# frontend.net
KiCad netlist of a schematic drawn in EAGLE
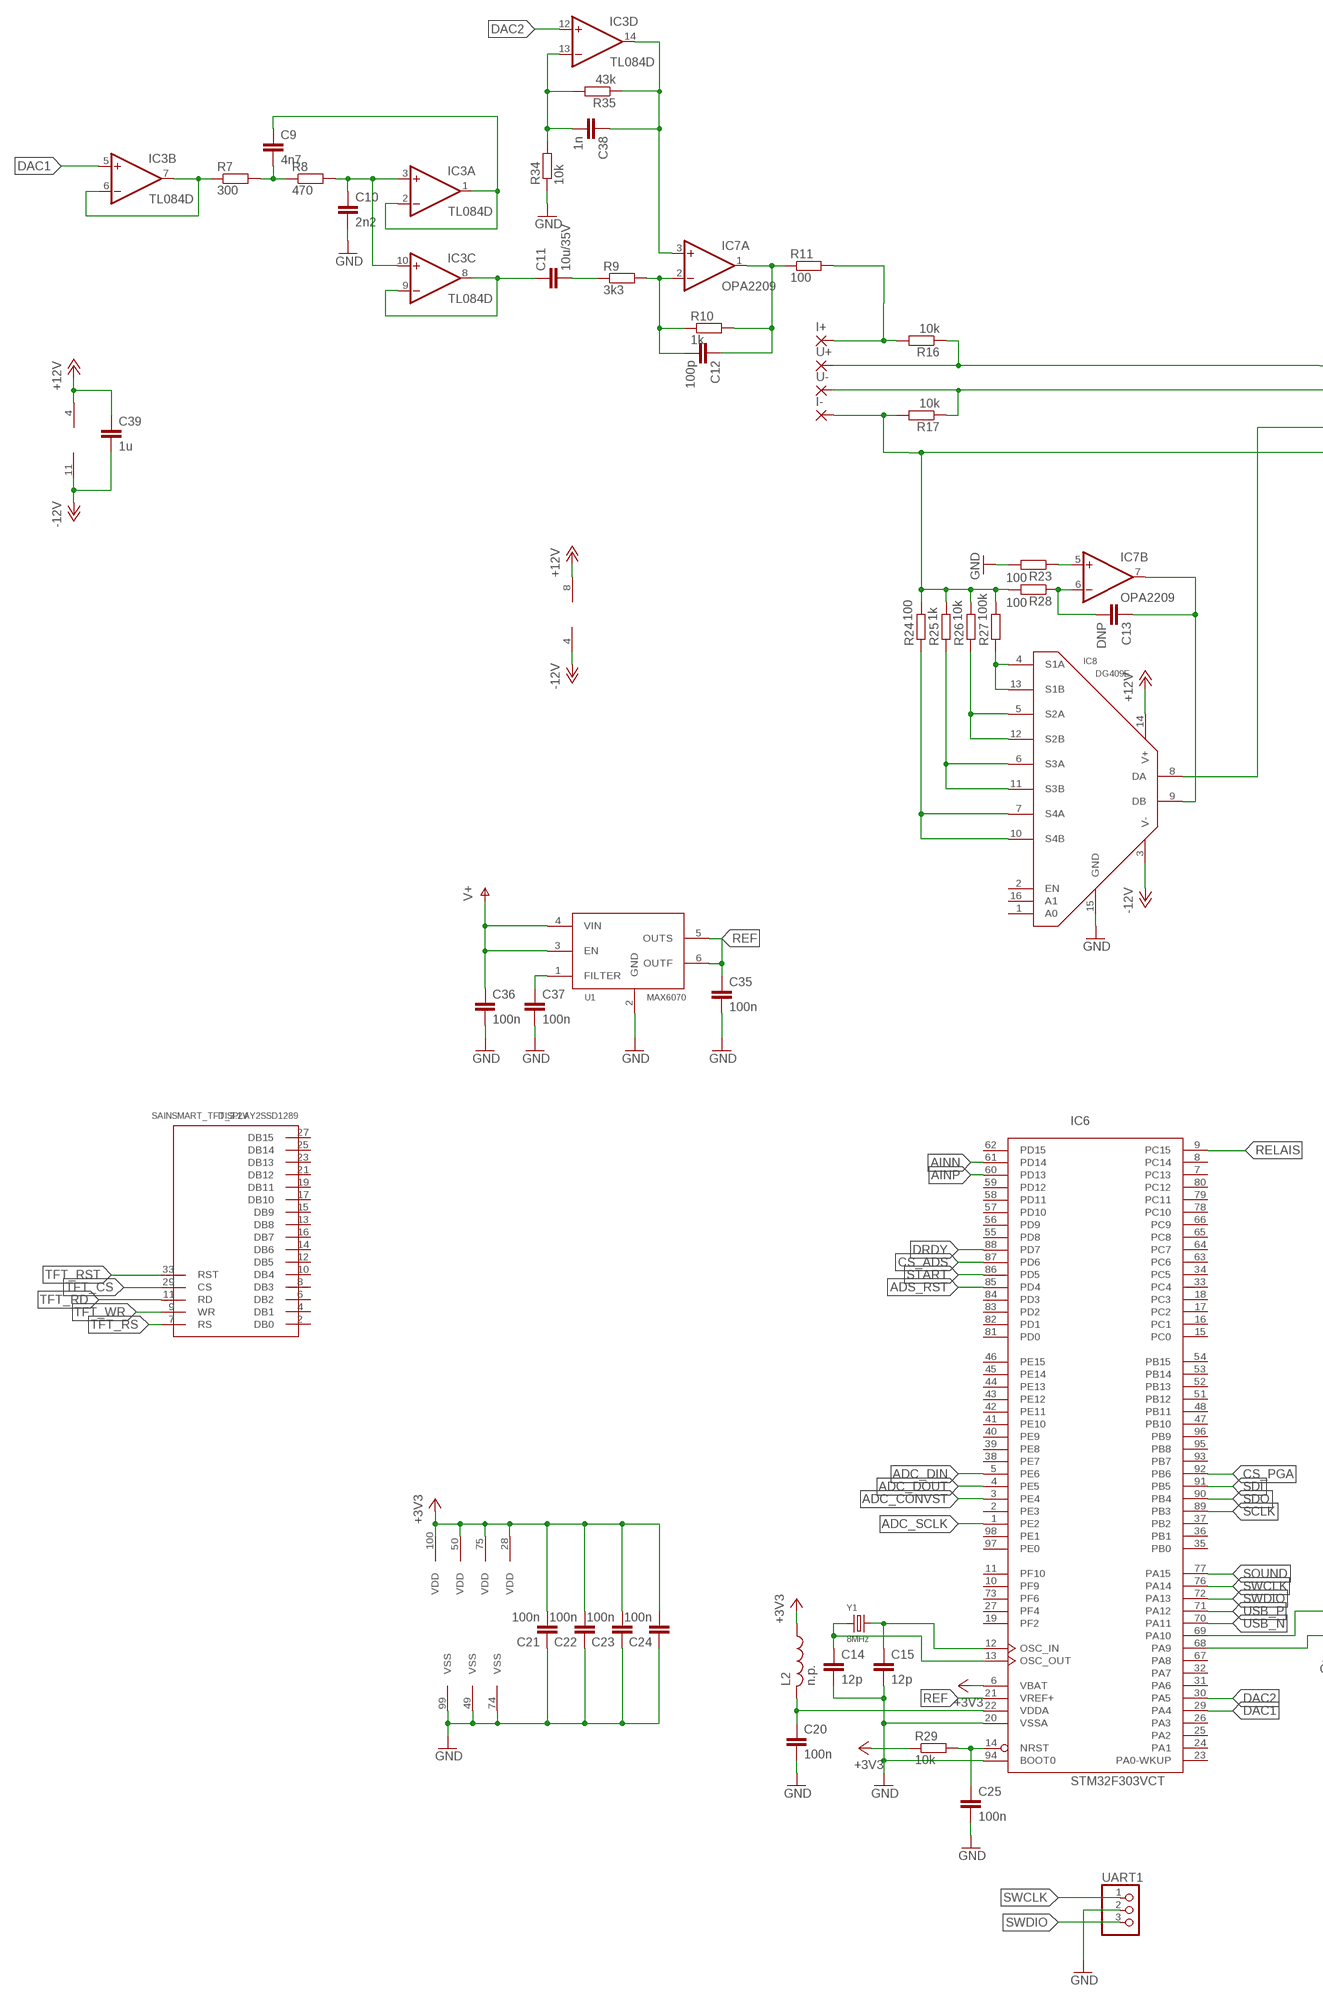
[diagram p0: schematic, sheet 1, part 1 of 2]
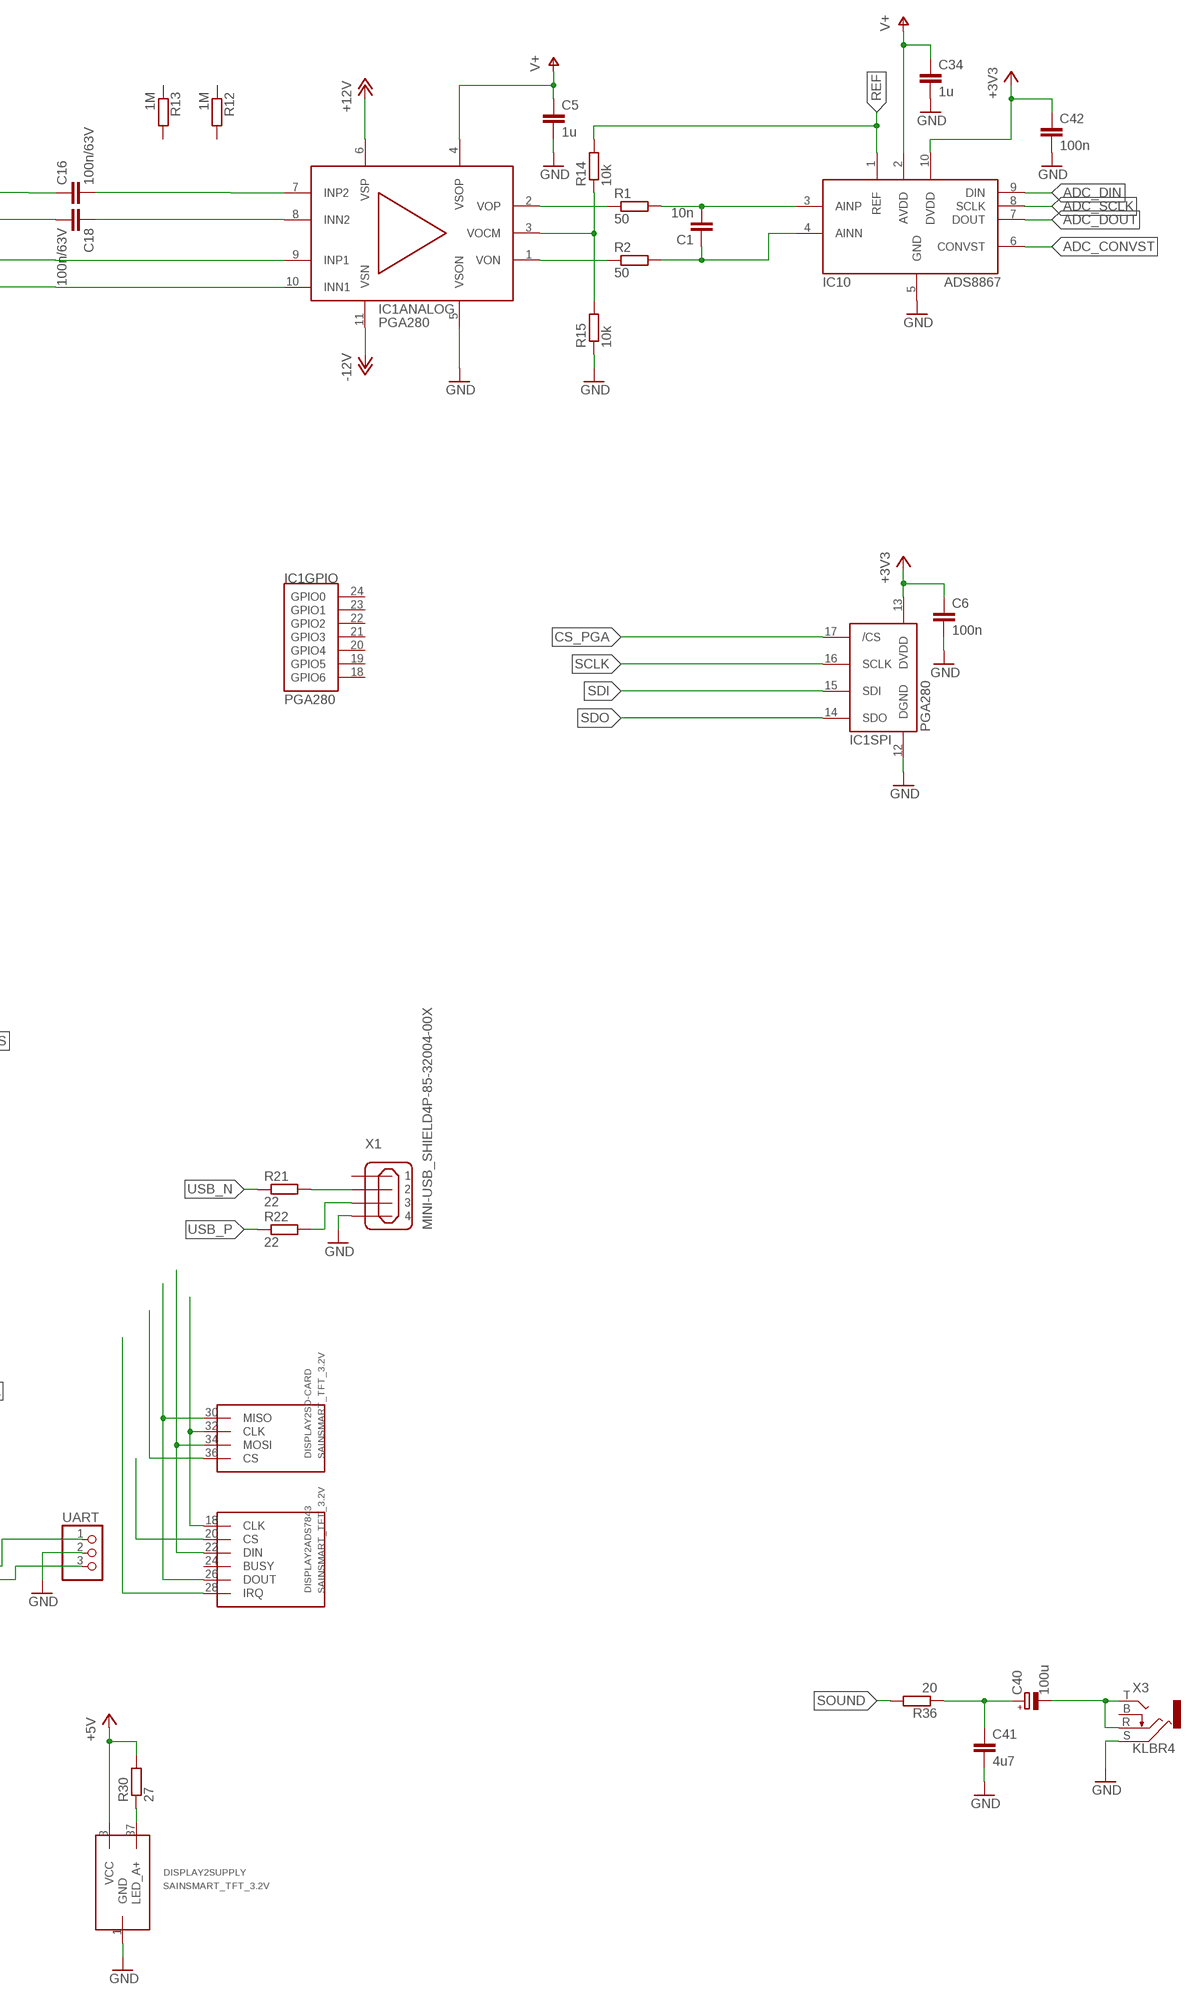
[diagram p1: schematic, sheet 1, part 2 of 2]
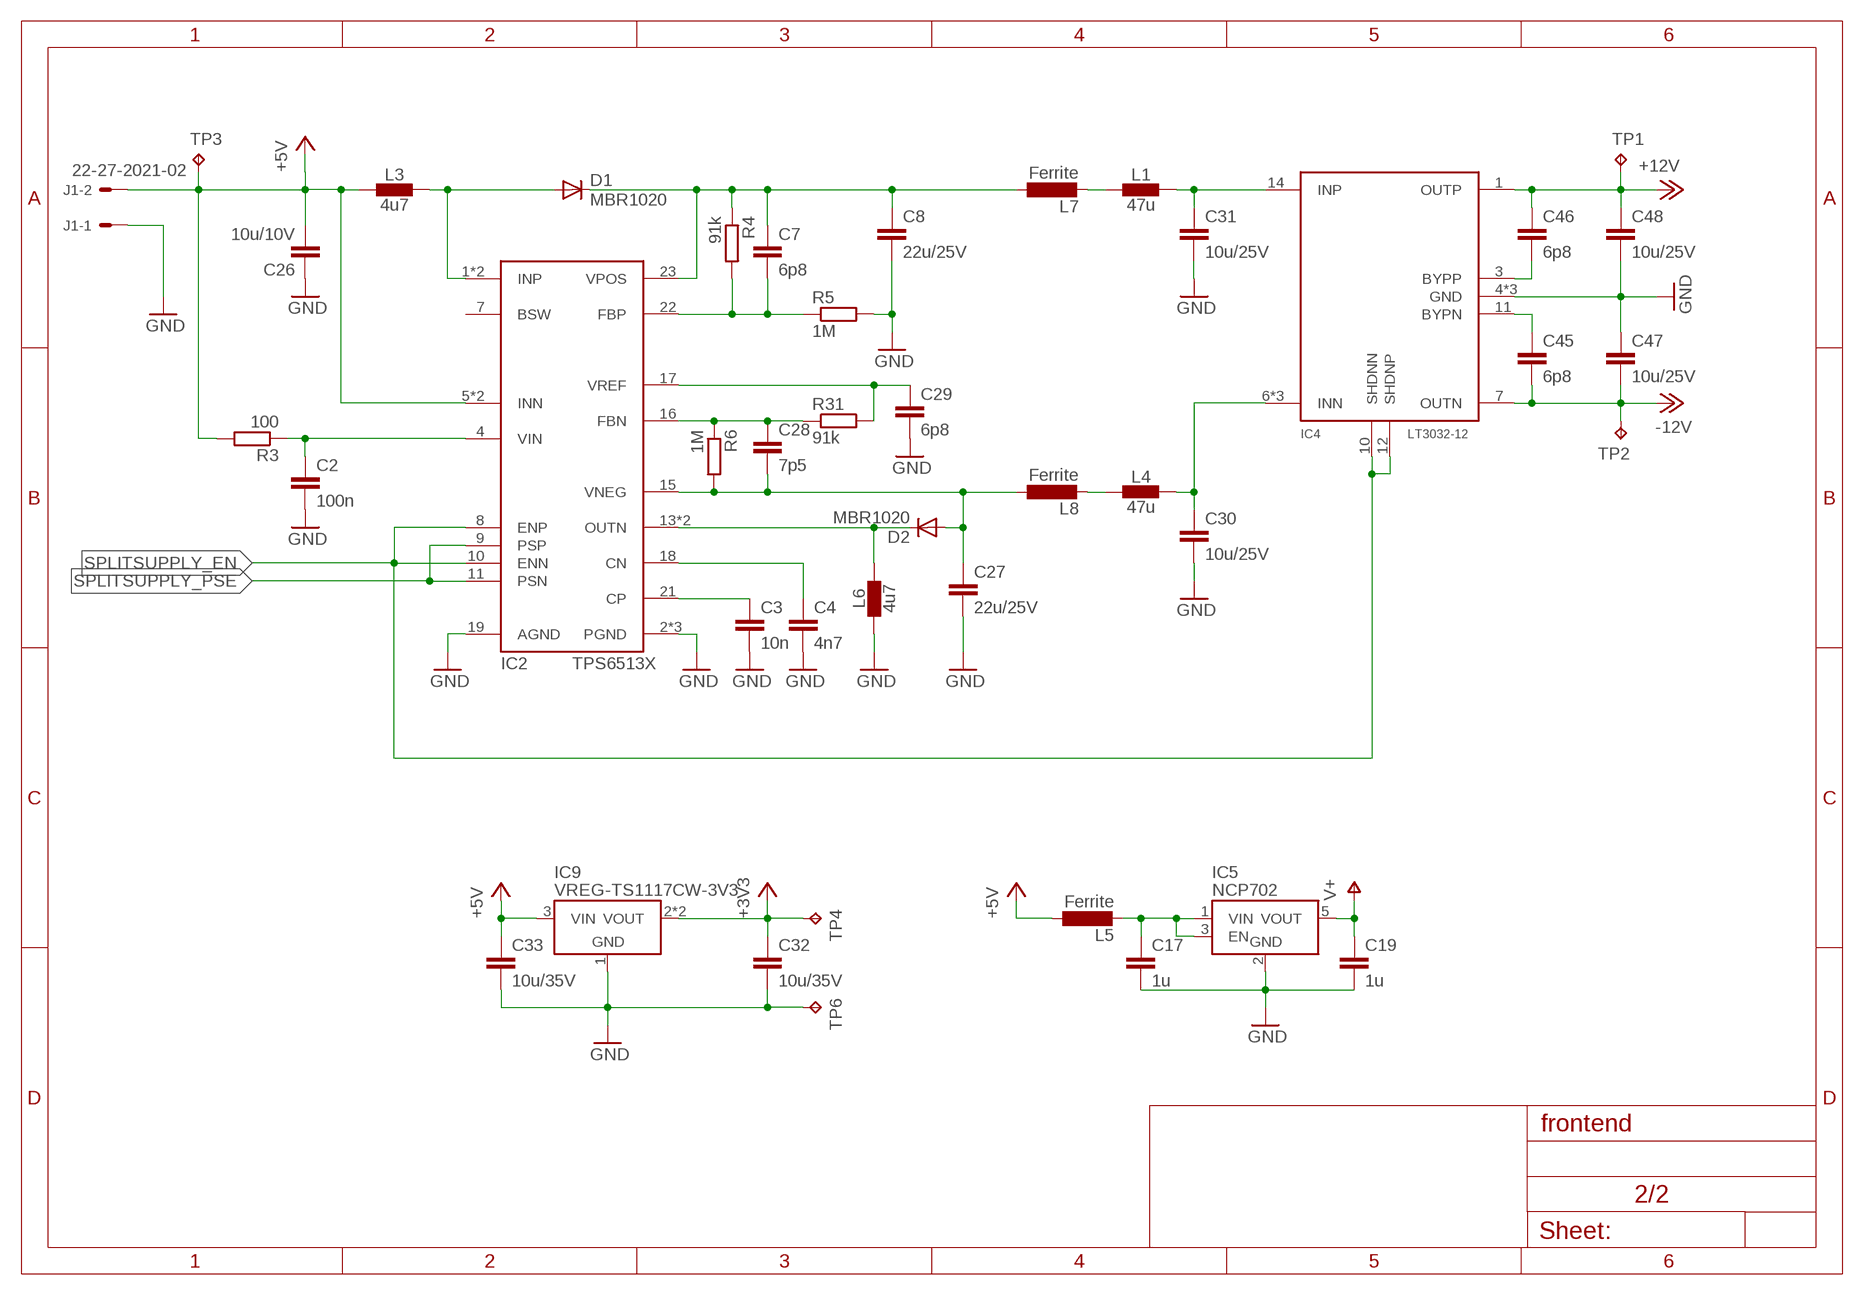
[diagram p2: schematic, sheet 2]

(export (version "E")
  (design (tool "Eeschema 10.0.6"))
  (components
    (comp (ref "C2")
      (value "100n")
      (footprint "eagle-import:C0603K")
      (libsource (lib "eagle-import") (part "C-EUC0603K"))
    )
    (comp (ref "C3")
      (value "10n")
      (footprint "eagle-import:C0603K")
      (libsource (lib "eagle-import") (part "C-EUC0603K"))
    )
    (comp (ref "C4")
      (value "4n7")
      (footprint "eagle-import:C0603K")
      (libsource (lib "eagle-import") (part "C-EUC0603K"))
    )
    (comp (ref "C7")
      (value "6p8")
      (footprint "eagle-import:C0603K")
      (libsource (lib "eagle-import") (part "C-EUC0603K"))
    )
    (comp (ref "C8")
      (value "22u/25V")
      (footprint "eagle-import:C1206K")
      (libsource (lib "eagle-import") (part "C-EUC1206K"))
    )
    (comp (ref "C17")
      (value "1u")
      (footprint "eagle-import:C0603")
      (libsource (lib "eagle-import") (part "C-EUC0603"))
    )
    (comp (ref "C19")
      (value "1u")
      (footprint "eagle-import:C0603")
      (libsource (lib "eagle-import") (part "C-EUC0603"))
    )
    (comp (ref "C26")
      (value "10u/10V")
      (footprint "eagle-import:C1206K")
      (libsource (lib "eagle-import") (part "C-EUC1206K"))
    )
    (comp (ref "C27")
      (value "22u/25V")
      (footprint "eagle-import:C1206K")
      (libsource (lib "eagle-import") (part "C-EUC1206K"))
    )
    (comp (ref "C28")
      (value "7p5")
      (footprint "eagle-import:C0603K")
      (libsource (lib "eagle-import") (part "C-EUC0603K"))
    )
    (comp (ref "C29")
      (value "6p8")
      (footprint "eagle-import:C0603K")
      (libsource (lib "eagle-import") (part "C-EUC0603K"))
    )
    (comp (ref "C30")
      (value "10u/25V")
      (footprint "eagle-import:C1206K")
      (libsource (lib "eagle-import") (part "C-EUC1206K"))
    )
    (comp (ref "C31")
      (value "10u/25V")
      (footprint "eagle-import:C1206K")
      (libsource (lib "eagle-import") (part "C-EUC1206K"))
    )
    (comp (ref "C32")
      (value "10u/35V")
      (footprint "eagle-import:C1206K")
      (libsource (lib "eagle-import") (part "C-EUC1206K"))
    )
    (comp (ref "C33")
      (value "10u/35V")
      (footprint "eagle-import:C1206K")
      (libsource (lib "eagle-import") (part "C-EUC1206K"))
    )
    (comp (ref "C45")
      (value "6p8")
      (footprint "eagle-import:C0603K")
      (libsource (lib "eagle-import") (part "C-EUC0603K"))
    )
    (comp (ref "C46")
      (value "6p8")
      (footprint "eagle-import:C0603K")
      (libsource (lib "eagle-import") (part "C-EUC0603K"))
    )
    (comp (ref "C47")
      (value "10u/25V")
      (footprint "eagle-import:C1206K")
      (libsource (lib "eagle-import") (part "C-EUC1206K"))
    )
    (comp (ref "C48")
      (value "10u/25V")
      (footprint "eagle-import:C1206K")
      (libsource (lib "eagle-import") (part "C-EUC1206K"))
    )
    (comp (ref "D1")
      (value "MBR1020")
      (footprint "eagle-import:SOD123")
      (libsource (lib "eagle-import") (part "DIODE-SOD123"))
    )
    (comp (ref "D2")
      (value "MBR1020")
      (footprint "eagle-import:SOD123")
      (libsource (lib "eagle-import") (part "DIODE-SOD123"))
    )
    (comp (ref "IC2")
      (value "TPS6513X")
      (footprint "eagle-import:QFN50P400X400X100-25T250N")
      (libsource (lib "eagle-import") (part "TPS6513X"))
    )
    (comp (ref "IC4")
      (value "LT3032-12")
      (footprint "eagle-import:SON50P300X400X80-14N")
      (libsource (lib "eagle-import") (part "LT3032"))
    )
    (comp (ref "IC5")
      (value "NCP702")
      (footprint "eagle-import:SOT95P240X110-5")
      (libsource (lib "eagle-import") (part "NCP702"))
    )
    (comp (ref "IC9")
      (value "VREG-TS1117CW-3V3")
      (footprint "eagle-import:SOT223")
      (libsource (lib "eagle-import") (part "VREG-TS1117CW-3V3"))
    )
    (comp (ref "J1")
      (value "22-27-2021-02")
      (footprint "eagle-import:6410-02")
      (libsource (lib "eagle-import") (part "22-?-0227-2021"))
    )
    (comp (ref "L1")
      (value "47u")
      (footprint "eagle-import:L_1212")
      (libsource (lib "eagle-import") (part "INDUCTOR-1212"))
    )
    (comp (ref "L3")
      (value "4u7")
      (footprint "eagle-import:L_1212")
      (libsource (lib "eagle-import") (part "INDUCTOR-1212"))
    )
    (comp (ref "L4")
      (value "47u")
      (footprint "eagle-import:L_1212")
      (libsource (lib "eagle-import") (part "INDUCTOR-1212"))
    )
    (comp (ref "L5")
      (value "Ferrite")
      (footprint "eagle-import:R0603")
      (libsource (lib "eagle-import") (part "INDUCTOR0603"))
    )
    (comp (ref "L6")
      (value "4u7")
      (footprint "eagle-import:L_1212")
      (libsource (lib "eagle-import") (part "INDUCTOR-1212"))
    )
    (comp (ref "L7")
      (value "Ferrite")
      (footprint "eagle-import:R0603")
      (libsource (lib "eagle-import") (part "INDUCTOR0603"))
    )
    (comp (ref "L8")
      (value "Ferrite")
      (footprint "eagle-import:R0603")
      (libsource (lib "eagle-import") (part "INDUCTOR0603"))
    )
    (comp (ref "R3")
      (value "100")
      (footprint "eagle-import:R0603")
      (libsource (lib "eagle-import") (part "R-EU_R0603"))
    )
    (comp (ref "R4")
      (value "91k")
      (footprint "eagle-import:R0603")
      (libsource (lib "eagle-import") (part "R-EU_R0603"))
    )
    (comp (ref "R5")
      (value "1M")
      (footprint "eagle-import:R0603")
      (libsource (lib "eagle-import") (part "R-EU_R0603"))
    )
    (comp (ref "R6")
      (value "1M")
      (footprint "eagle-import:R0603")
      (libsource (lib "eagle-import") (part "R-EU_R0603"))
    )
    (comp (ref "R31")
      (value "91k")
      (footprint "eagle-import:R0603")
      (libsource (lib "eagle-import") (part "R-EU_R0603"))
    )
    (comp (ref "TP1")
      (value "TPB2,54")
      (footprint "eagle-import:B2,54")
      (libsource (lib "eagle-import") (part "TPB2,54"))
    )
    (comp (ref "TP2")
      (value "TPB2,54")
      (footprint "eagle-import:B2,54")
      (libsource (lib "eagle-import") (part "TPB2,54"))
    )
    (comp (ref "TP3")
      (value "TPB2,54")
      (footprint "eagle-import:B2,54")
      (libsource (lib "eagle-import") (part "TPB2,54"))
    )
    (comp (ref "TP4")
      (value "TPB2,54")
      (footprint "eagle-import:B2,54")
      (libsource (lib "eagle-import") (part "TPB2,54"))
    )
    (comp (ref "TP6")
      (value "TPB2,54")
      (footprint "eagle-import:B2,54")
      (libsource (lib "eagle-import") (part "TPB2,54"))
    )
    (comp (ref "C1")
      (value "10n")
      (footprint "eagle-import:C0603K")
      (libsource (lib "eagle-import") (part "C-EUC0603K"))
    )
    (comp (ref "C5")
      (value "1u")
      (footprint "eagle-import:C0603K")
      (libsource (lib "eagle-import") (part "C-EUC0603K"))
    )
    (comp (ref "C6")
      (value "100n")
      (footprint "eagle-import:C0603K")
      (libsource (lib "eagle-import") (part "C-EUC0603K"))
    )
    (comp (ref "C9")
      (value "4n7")
      (footprint "eagle-import:C0603K")
      (libsource (lib "eagle-import") (part "C-EUC0603K"))
    )
    (comp (ref "C10")
      (value "2n2")
      (footprint "eagle-import:C0603K")
      (libsource (lib "eagle-import") (part "C-EUC0603K"))
    )
    (comp (ref "C11")
      (value "10u/35V")
      (footprint "eagle-import:C1206K")
      (libsource (lib "eagle-import") (part "C-EUC1206K"))
    )
    (comp (ref "C12")
      (value "100p")
      (footprint "eagle-import:C0603K")
      (libsource (lib "eagle-import") (part "C-EUC0603K"))
    )
    (comp (ref "C13")
      (value "DNP")
      (footprint "eagle-import:C0603K")
      (libsource (lib "eagle-import") (part "C-EUC0603K"))
    )
    (comp (ref "C14")
      (value "12p")
      (footprint "eagle-import:C0603K")
      (libsource (lib "eagle-import") (part "C-EUC0603K"))
    )
    (comp (ref "C15")
      (value "12p")
      (footprint "eagle-import:C0603K")
      (libsource (lib "eagle-import") (part "C-EUC0603K"))
    )
    (comp (ref "C16")
      (value "100n/63V")
      (footprint "eagle-import:C1206K")
      (libsource (lib "eagle-import") (part "C-EUC1206K"))
    )
    (comp (ref "C18")
      (value "100n/63V")
      (footprint "eagle-import:C1206K")
      (libsource (lib "eagle-import") (part "C-EUC1206K"))
    )
    (comp (ref "C20")
      (value "100n")
      (footprint "eagle-import:C0603K")
      (libsource (lib "eagle-import") (part "C-EUC0603K"))
    )
    (comp (ref "C21")
      (value "100n")
      (footprint "eagle-import:C0603K")
      (libsource (lib "eagle-import") (part "C-EUC0603K"))
    )
    (comp (ref "C22")
      (value "100n")
      (footprint "eagle-import:C0603K")
      (libsource (lib "eagle-import") (part "C-EUC0603K"))
    )
    (comp (ref "C23")
      (value "100n")
      (footprint "eagle-import:C0603K")
      (libsource (lib "eagle-import") (part "C-EUC0603K"))
    )
    (comp (ref "C24")
      (value "100n")
      (footprint "eagle-import:C0603K")
      (libsource (lib "eagle-import") (part "C-EUC0603K"))
    )
    (comp (ref "C25")
      (value "100n")
      (footprint "eagle-import:C0603K")
      (libsource (lib "eagle-import") (part "C-EUC0603K"))
    )
    (comp (ref "C34")
      (value "1u")
      (footprint "eagle-import:C0603K")
      (libsource (lib "eagle-import") (part "C-EUC0603K"))
    )
    (comp (ref "C35")
      (value "100n")
      (footprint "eagle-import:C0603K")
      (libsource (lib "eagle-import") (part "C-EUC0603K"))
    )
    (comp (ref "C36")
      (value "100n")
      (footprint "eagle-import:C0603K")
      (libsource (lib "eagle-import") (part "C-EUC0603K"))
    )
    (comp (ref "C37")
      (value "100n")
      (footprint "eagle-import:C0603K")
      (libsource (lib "eagle-import") (part "C-EUC0603K"))
    )
    (comp (ref "C38")
      (value "1n")
      (footprint "eagle-import:C0603K")
      (libsource (lib "eagle-import") (part "C-EUC0603K"))
    )
    (comp (ref "C39")
      (value "1u")
      (footprint "eagle-import:C0603K")
      (libsource (lib "eagle-import") (part "C-EUC0603K"))
    )
    (comp (ref "C40")
      (value "100u")
      (footprint "eagle-import:E2,5-5")
      (libsource (lib "eagle-import") (part "CPOL-EUE2.5-5"))
    )
    (comp (ref "C41")
      (value "4u7")
      (footprint "eagle-import:C1206K")
      (libsource (lib "eagle-import") (part "C-EUC1206K"))
    )
    (comp (ref "C42")
      (value "100n")
      (footprint "eagle-import:C0603K")
      (libsource (lib "eagle-import") (part "C-EUC0603K"))
    )
    (comp (ref "DISPLAY2")
      (value "SAINSMART_TFT_3.2V")
      (footprint "eagle-import:SAINSMART_ANGLED")
      (libsource (lib "eagle-import") (part "SAINSMART_TFT_3.2V"))
    )
    (comp (ref "I+")
      (value "SMD5")
      (footprint "eagle-import:SMD2,54-5,08")
      (libsource (lib "eagle-import") (part "SMD5"))
    )
    (comp (ref "I-")
      (value "SMD5")
      (footprint "eagle-import:SMD2,54-5,08")
      (libsource (lib "eagle-import") (part "SMD5"))
    )
    (comp (ref "IC1")
      (value "PGA280")
      (footprint "eagle-import:TSSOP24")
      (libsource (lib "eagle-import") (part "PGA280"))
    )
    (comp (ref "IC3")
      (value "TL084D")
      (footprint "eagle-import:SO14")
      (libsource (lib "eagle-import") (part "TL084D"))
    )
    (comp (ref "IC6")
      (value "STM32F303VCT")
      (footprint "eagle-import:LQFP100")
      (libsource (lib "eagle-import") (part "STM32F303VTC"))
    )
    (comp (ref "IC7")
      (value "OPA2209")
      (footprint "eagle-import:SO08")
      (libsource (lib "eagle-import") (part "TL082D"))
    )
    (comp (ref "IC8")
      (value "DG409E")
      (footprint "eagle-import:TSSOP16")
      (libsource (lib "eagle-import") (part "DG409E"))
    )
    (comp (ref "IC10")
      (value "ADS8867")
      (footprint "eagle-import:SOP50P490X110-10N")
      (libsource (lib "eagle-import") (part "ADS8867"))
    )
    (comp (ref "L2")
      (value "n.p.")
      (footprint "eagle-import:R0603")
      (libsource (lib "eagle-import") (part "xmaker_INDUCTOR0603"))
    )
    (comp (ref "R1")
      (value "50")
      (footprint "eagle-import:R0603")
      (libsource (lib "eagle-import") (part "resistor_R-EU_R0603"))
    )
    (comp (ref "R2")
      (value "50")
      (footprint "eagle-import:R0603")
      (libsource (lib "eagle-import") (part "resistor_R-EU_R0603"))
    )
    (comp (ref "R7")
      (value "300")
      (footprint "eagle-import:R0603")
      (libsource (lib "eagle-import") (part "R-EU_R0603"))
    )
    (comp (ref "R8")
      (value "470")
      (footprint "eagle-import:R0603")
      (libsource (lib "eagle-import") (part "R-EU_R0603"))
    )
    (comp (ref "R9")
      (value "3k3")
      (footprint "eagle-import:R0603")
      (libsource (lib "eagle-import") (part "R-EU_R0603"))
    )
    (comp (ref "R10")
      (value "1k")
      (footprint "eagle-import:R0603")
      (libsource (lib "eagle-import") (part "R-EU_R0603"))
    )
    (comp (ref "R11")
      (value "100")
      (footprint "eagle-import:R0603")
      (libsource (lib "eagle-import") (part "R-EU_R0603"))
    )
    (comp (ref "R12")
      (value "1M")
      (footprint "eagle-import:R0603")
      (libsource (lib "eagle-import") (part "R-EU_R0603"))
    )
    (comp (ref "R13")
      (value "1M")
      (footprint "eagle-import:R0603")
      (libsource (lib "eagle-import") (part "R-EU_R0603"))
    )
    (comp (ref "R14")
      (value "10k")
      (footprint "eagle-import:R0603")
      (libsource (lib "eagle-import") (part "resistor_R-EU_R0603"))
    )
    (comp (ref "R15")
      (value "10k")
      (footprint "eagle-import:R0603")
      (libsource (lib "eagle-import") (part "resistor_R-EU_R0603"))
    )
    (comp (ref "R16")
      (value "10k")
      (footprint "eagle-import:R0603")
      (libsource (lib "eagle-import") (part "resistor_R-EU_R0603"))
    )
    (comp (ref "R17")
      (value "10k")
      (footprint "eagle-import:R0603")
      (libsource (lib "eagle-import") (part "resistor_R-EU_R0603"))
    )
    (comp (ref "R21")
      (value "22")
      (footprint "eagle-import:R0603")
      (libsource (lib "eagle-import") (part "resistor_R-EU_R0603"))
    )
    (comp (ref "R22")
      (value "22")
      (footprint "eagle-import:R0603")
      (libsource (lib "eagle-import") (part "resistor_R-EU_R0603"))
    )
    (comp (ref "R23")
      (value "100")
      (footprint "eagle-import:R0603")
      (libsource (lib "eagle-import") (part "R-EU_R0603"))
    )
    (comp (ref "R24")
      (value "100")
      (footprint "eagle-import:R0603")
      (libsource (lib "eagle-import") (part "R-EU_R0603"))
    )
    (comp (ref "R25")
      (value "1k")
      (footprint "eagle-import:R0603")
      (libsource (lib "eagle-import") (part "R-EU_R0603"))
    )
    (comp (ref "R26")
      (value "10k")
      (footprint "eagle-import:R0603")
      (libsource (lib "eagle-import") (part "R-EU_R0603"))
    )
    (comp (ref "R27")
      (value "100k")
      (footprint "eagle-import:R0603")
      (libsource (lib "eagle-import") (part "R-EU_R0603"))
    )
    (comp (ref "R28")
      (value "100")
      (footprint "eagle-import:R0603")
      (libsource (lib "eagle-import") (part "R-EU_R0603"))
    )
    (comp (ref "R29")
      (value "10k")
      (footprint "eagle-import:R0603")
      (libsource (lib "eagle-import") (part "resistor_R-EU_R0603"))
    )
    (comp (ref "R30")
      (value "27")
      (footprint "eagle-import:R1206")
      (libsource (lib "eagle-import") (part "resistor_R-EU_R1206"))
    )
    (comp (ref "R34")
      (value "10k")
      (footprint "eagle-import:R0603")
      (libsource (lib "eagle-import") (part "R-EU_R0603"))
    )
    (comp (ref "R35")
      (value "43k")
      (footprint "eagle-import:R0603")
      (libsource (lib "eagle-import") (part "R-EU_R0603"))
    )
    (comp (ref "R36")
      (value "20")
      (footprint "eagle-import:R1206")
      (libsource (lib "eagle-import") (part "R-EU_R1206"))
    )
    (comp (ref "U+")
      (value "SMD5")
      (footprint "eagle-import:SMD2,54-5,08")
      (libsource (lib "eagle-import") (part "SMD5"))
    )
    (comp (ref "U-")
      (value "SMD5")
      (footprint "eagle-import:SMD2,54-5,08")
      (libsource (lib "eagle-import") (part "SMD5"))
    )
    (comp (ref "U1")
      (value "MAX6070")
      (footprint "eagle-import:SOT23-6L")
      (libsource (lib "eagle-import") (part "MAX6070"))
    )
    (comp (ref "UART")
      (value "PINHD-1X3")
      (footprint "eagle-import:1X03")
      (libsource (lib "eagle-import") (part "PINHD-1X3"))
    )
    (comp (ref "UART1")
      (value "PINHD-1X3")
      (footprint "eagle-import:1X03")
      (libsource (lib "eagle-import") (part "PINHD-1X3"))
    )
    (comp (ref "X1")
      (value "MINI-USB_SHIELD4P-85-32004-00X")
      (footprint "eagle-import:85-32004-00X")
      (libsource (lib "eagle-import") (part "MINI-USB_SHIELD4P-85-32004-00X"))
    )
    (comp (ref "X3")
      (value "KLBR4")
      (footprint "eagle-import:KLBR4")
      (fields (field (name "MPN") "KLBR 4"))
      (libsource (lib "eagle-import") (part "KLBR4"))
    )
    (comp (ref "Y1")
      (value "8MHz")
      (footprint "eagle-import:3.2X2.5MM")
      (libsource (lib "eagle-import") (part "CRYSTAL.3.2X2.5MM"))
    )
  )
  (nets
    (net (code "1") (name "+3V3") (class "Default")
      (node (ref "C21") (pin "2") (pinfunction "2_2") (pintype "passive"))
      (node (ref "C22") (pin "2") (pinfunction "2_2") (pintype "passive"))
      (node (ref "C23") (pin "2") (pinfunction "2_2") (pintype "passive"))
      (node (ref "C24") (pin "2") (pinfunction "2_2") (pintype "passive"))
      (node (ref "C32") (pin "1") (pinfunction "1_1") (pintype "passive"))
      (node (ref "C42") (pin "1") (pinfunction "1_1") (pintype "passive"))
      (node (ref "C6") (pin "1") (pinfunction "1_1") (pintype "passive"))
      (node (ref "IC1") (pin "13") (pinfunction "DVDD_13") (pintype "bidirectional"))
      (node (ref "IC10") (pin "10") (pinfunction "DVDD_10") (pintype "bidirectional"))
      (node (ref "IC6") (pin "100") (pinfunction "VDD_100") (pintype "power_in"))
      (node (ref "IC6") (pin "28") (pinfunction "VDD_28") (pintype "power_in"))
      (node (ref "IC6") (pin "50") (pinfunction "VDD_50") (pintype "power_in"))
      (node (ref "IC6") (pin "6") (pinfunction "VBAT_6") (pintype "power_in"))
      (node (ref "IC6") (pin "75") (pinfunction "VDD_75") (pintype "power_in"))
      (node (ref "IC9") (pin "2") (pinfunction "VOUT_2") (pintype "power_in"))
      (node (ref "IC9") (pin "4") (pinfunction "VOUT_4") (pintype "power_in"))
      (node (ref "L2") (pin "1") (pinfunction "1_1") (pintype "passive"))
      (node (ref "R29") (pin "1") (pinfunction "1_1") (pintype "passive"))
      (node (ref "TP4") (pin "TP") (pinfunction "TP_TP") (pintype "input"))
    )
    (net (code "2") (name "+5V") (class "Default")
      (node (ref "C26") (pin "2") (pinfunction "2_2") (pintype "passive"))
      (node (ref "C33") (pin "1") (pinfunction "1_1") (pintype "passive"))
      (node (ref "DISPLAY2") (pin "3") (pinfunction "VCC_3") (pintype "bidirectional"))
      (node (ref "IC2") (pin "5") (pinfunction "INN_5") (pintype "bidirectional"))
      (node (ref "IC2") (pin "6") (pinfunction "INN_6") (pintype "bidirectional"))
      (node (ref "IC9") (pin "3") (pinfunction "VIN_3") (pintype "power_in"))
      (node (ref "J1") (pin "2") (pinfunction "S_2") (pintype "passive"))
      (node (ref "L3") (pin "1") (pinfunction "1_1") (pintype "passive"))
      (node (ref "L5") (pin "1") (pinfunction "1_1") (pintype "passive"))
      (node (ref "R3") (pin "2") (pinfunction "2_2") (pintype "passive"))
      (node (ref "R30") (pin "2") (pinfunction "2_2") (pintype "passive"))
      (node (ref "TP3") (pin "TP") (pinfunction "TP_TP") (pintype "input"))
    )
    (net (code "3") (name "+12V") (class "Default")
      (node (ref "C39") (pin "1") (pinfunction "1_1") (pintype "passive"))
      (node (ref "C46") (pin "1") (pinfunction "1_1") (pintype "passive"))
      (node (ref "C48") (pin "1") (pinfunction "1_1") (pintype "passive"))
      (node (ref "IC1") (pin "6") (pinfunction "VSP_6") (pintype "bidirectional"))
      (node (ref "IC3") (pin "4") (pinfunction "V+_4") (pintype "power_in"))
      (node (ref "IC4") (pin "1") (pinfunction "OUTP_1") (pintype "bidirectional"))
      (node (ref "IC7") (pin "8") (pinfunction "V+_8") (pintype "power_in"))
      (node (ref "IC8") (pin "14") (pinfunction "V+_14") (pintype "bidirectional"))
      (node (ref "TP1") (pin "TP") (pinfunction "TP_TP") (pintype "input"))
    )
    (net (code "4") (name "-12V") (class "Default")
      (node (ref "C39") (pin "2") (pinfunction "2_2") (pintype "passive"))
      (node (ref "C45") (pin "2") (pinfunction "2_2") (pintype "passive"))
      (node (ref "C47") (pin "2") (pinfunction "2_2") (pintype "passive"))
      (node (ref "IC1") (pin "11") (pinfunction "VSN_11") (pintype "bidirectional"))
      (node (ref "IC3") (pin "11") (pinfunction "V-_11") (pintype "power_in"))
      (node (ref "IC4") (pin "7") (pinfunction "OUTN_7") (pintype "bidirectional"))
      (node (ref "IC7") (pin "4") (pinfunction "V-_4") (pintype "power_in"))
      (node (ref "IC8") (pin "3") (pinfunction "V-_3") (pintype "bidirectional"))
      (node (ref "TP2") (pin "TP") (pinfunction "TP_TP") (pintype "input"))
    )
    (net (code "5") (name "ADC_CONVST") (class "Default")
      (node (ref "IC10") (pin "6") (pinfunction "CONVST_6") (pintype "bidirectional"))
      (node (ref "IC6") (pin "3") (pinfunction "PE4_3") (pintype "bidirectional"))
    )
    (net (code "6") (name "ADC_DIN") (class "Default")
      (node (ref "IC10") (pin "9") (pinfunction "DIN_9") (pintype "bidirectional"))
      (node (ref "IC6") (pin "5") (pinfunction "PE6_5") (pintype "bidirectional"))
    )
    (net (code "7") (name "ADC_DOUT") (class "Default")
      (node (ref "IC10") (pin "7") (pinfunction "DOUT_7") (pintype "bidirectional"))
      (node (ref "IC6") (pin "4") (pinfunction "PE5_4") (pintype "bidirectional"))
    )
    (net (code "8") (name "ADC_SCLK") (class "Default")
      (node (ref "IC10") (pin "8") (pinfunction "SCLK_8") (pintype "bidirectional"))
      (node (ref "IC6") (pin "1") (pinfunction "PE2_1") (pintype "bidirectional"))
    )
    (net (code "9") (name "ADS_RST") (class "Default")
      (node (ref "IC6") (pin "85") (pinfunction "PD4_85") (pintype "bidirectional"))
    )
    (net (code "10") (name "AINN") (class "Default")
      (node (ref "C1") (pin "1") (pinfunction "1_1") (pintype "passive"))
      (node (ref "IC10") (pin "4") (pinfunction "AINN_4") (pintype "bidirectional"))
      (node (ref "IC6") (pin "61") (pinfunction "PD14_61") (pintype "bidirectional"))
      (node (ref "R2") (pin "2") (pinfunction "2_2") (pintype "passive"))
    )
    (net (code "11") (name "AINP") (class "Default")
      (node (ref "C1") (pin "2") (pinfunction "2_2") (pintype "passive"))
      (node (ref "IC10") (pin "3") (pinfunction "AINP_3") (pintype "bidirectional"))
      (node (ref "IC6") (pin "60") (pinfunction "PD13_60") (pintype "bidirectional"))
      (node (ref "R1") (pin "2") (pinfunction "2_2") (pintype "passive"))
    )
    (net (code "12") (name "CS_ADS") (class "Default")
      (node (ref "IC6") (pin "87") (pinfunction "PD6_87") (pintype "bidirectional"))
    )
    (net (code "13") (name "CS_PGA") (class "Default")
      (node (ref "IC1") (pin "17") (pinfunction "/CS_17") (pintype "bidirectional"))
      (node (ref "IC6") (pin "92") (pinfunction "PB6_92") (pintype "bidirectional"))
    )
    (net (code "14") (name "DAC1") (class "Default")
      (node (ref "IC3") (pin "5") (pinfunction "+IN_5") (pintype "input"))
      (node (ref "IC6") (pin "29") (pinfunction "PA4_29") (pintype "bidirectional"))
    )
    (net (code "15") (name "DAC2") (class "Default")
      (node (ref "IC3") (pin "12") (pinfunction "+IN_12") (pintype "input"))
      (node (ref "IC6") (pin "30") (pinfunction "PA5_30") (pintype "bidirectional"))
    )
    (net (code "16") (name "DRDY") (class "Default")
      (node (ref "IC6") (pin "88") (pinfunction "PD7_88") (pintype "bidirectional"))
    )
    (net (code "17") (name "GND") (class "Default")
      (node (ref "C10") (pin "2") (pinfunction "2_2") (pintype "passive"))
      (node (ref "C14") (pin "2") (pinfunction "2_2") (pintype "passive"))
      (node (ref "C15") (pin "2") (pinfunction "2_2") (pintype "passive"))
      (node (ref "C17") (pin "2") (pinfunction "2_2") (pintype "passive"))
      (node (ref "C19") (pin "2") (pinfunction "2_2") (pintype "passive"))
      (node (ref "C2") (pin "2") (pinfunction "2_2") (pintype "passive"))
      (node (ref "C20") (pin "2") (pinfunction "2_2") (pintype "passive"))
      (node (ref "C21") (pin "1") (pinfunction "1_1") (pintype "passive"))
      (node (ref "C22") (pin "1") (pinfunction "1_1") (pintype "passive"))
      (node (ref "C23") (pin "1") (pinfunction "1_1") (pintype "passive"))
      (node (ref "C24") (pin "1") (pinfunction "1_1") (pintype "passive"))
      (node (ref "C25") (pin "2") (pinfunction "2_2") (pintype "passive"))
      (node (ref "C26") (pin "1") (pinfunction "1_1") (pintype "passive"))
      (node (ref "C27") (pin "2") (pinfunction "2_2") (pintype "passive"))
      (node (ref "C29") (pin "2") (pinfunction "2_2") (pintype "passive"))
      (node (ref "C3") (pin "2") (pinfunction "2_2") (pintype "passive"))
      (node (ref "C30") (pin "2") (pinfunction "2_2") (pintype "passive"))
      (node (ref "C31") (pin "2") (pinfunction "2_2") (pintype "passive"))
      (node (ref "C32") (pin "2") (pinfunction "2_2") (pintype "passive"))
      (node (ref "C33") (pin "2") (pinfunction "2_2") (pintype "passive"))
      (node (ref "C34") (pin "2") (pinfunction "2_2") (pintype "passive"))
      (node (ref "C35") (pin "2") (pinfunction "2_2") (pintype "passive"))
      (node (ref "C36") (pin "2") (pinfunction "2_2") (pintype "passive"))
      (node (ref "C37") (pin "2") (pinfunction "2_2") (pintype "passive"))
      (node (ref "C4") (pin "2") (pinfunction "2_2") (pintype "passive"))
      (node (ref "C41") (pin "2") (pinfunction "2_2") (pintype "passive"))
      (node (ref "C42") (pin "2") (pinfunction "2_2") (pintype "passive"))
      (node (ref "C47") (pin "1") (pinfunction "1_1") (pintype "passive"))
      (node (ref "C48") (pin "2") (pinfunction "2_2") (pintype "passive"))
      (node (ref "C5") (pin "2") (pinfunction "2_2") (pintype "passive"))
      (node (ref "C6") (pin "2") (pinfunction "2_2") (pintype "passive"))
      (node (ref "C8") (pin "2") (pinfunction "2_2") (pintype "passive"))
      (node (ref "DISPLAY2") (pin "1") (pinfunction "GND_1") (pintype "bidirectional"))
      (node (ref "IC1") (pin "12") (pinfunction "DGND_12") (pintype "bidirectional"))
      (node (ref "IC1") (pin "5") (pinfunction "VSON_5") (pintype "bidirectional"))
      (node (ref "IC10") (pin "5") (pinfunction "GND_5") (pintype "bidirectional"))
      (node (ref "IC2") (pin "19") (pinfunction "AGND_19") (pintype "bidirectional"))
      (node (ref "IC2") (pin "2") (pinfunction "PGND_2") (pintype "bidirectional"))
      (node (ref "IC2") (pin "25") (pinfunction "PGND_25") (pintype "bidirectional"))
      (node (ref "IC2") (pin "3") (pinfunction "PGND_3") (pintype "bidirectional"))
      (node (ref "IC4") (pin "4") (pinfunction "GND_4") (pintype "bidirectional"))
      (node (ref "IC4") (pin "5") (pinfunction "GND_5") (pintype "bidirectional"))
      (node (ref "IC4") (pin "EP4") (pinfunction "GND_EP4") (pintype "bidirectional"))
      (node (ref "IC5") (pin "2") (pinfunction "GND_2") (pintype "power_in"))
      (node (ref "IC6") (pin "20") (pinfunction "VSSA_20") (pintype "power_in"))
      (node (ref "IC6") (pin "49") (pinfunction "VSS_49") (pintype "power_in"))
      (node (ref "IC6") (pin "74") (pinfunction "VSS_74") (pintype "power_in"))
      (node (ref "IC6") (pin "94") (pinfunction "BOOT0_94") (pintype "input"))
      (node (ref "IC6") (pin "99") (pinfunction "VSS_99") (pintype "power_in"))
      (node (ref "IC8") (pin "15") (pinfunction "GND_15") (pintype "bidirectional"))
      (node (ref "IC9") (pin "1") (pinfunction "GND_1") (pintype "power_in"))
      (node (ref "J1") (pin "1") (pinfunction "S_1") (pintype "passive"))
      (node (ref "L6") (pin "1") (pinfunction "1_1") (pintype "passive"))
      (node (ref "R15") (pin "1") (pinfunction "1_1") (pintype "passive"))
      (node (ref "R23") (pin "2") (pinfunction "2_2") (pintype "passive"))
      (node (ref "R34") (pin "1") (pinfunction "1_1") (pintype "passive"))
      (node (ref "R5") (pin "2") (pinfunction "2_2") (pintype "passive"))
      (node (ref "TP6") (pin "TP") (pinfunction "TP_TP") (pintype "input"))
      (node (ref "U1") (pin "2") (pinfunction "GND_2") (pintype "bidirectional"))
      (node (ref "UART") (pin "2") (pinfunction "2_2") (pintype "passive"))
      (node (ref "UART1") (pin "2") (pinfunction "2_2") (pintype "passive"))
      (node (ref "X1") (pin "4") (pinfunction "4_4") (pintype "passive"))
      (node (ref "X3") (pin "S") (pinfunction "S_S") (pintype "passive"))
    )
    (net (code "18") (name "Net-(C9-Pad2)") (class "Default")
      (node (ref "C9") (pin "2") (pinfunction "2_2") (pintype "passive"))
      (node (ref "R7") (pin "2") (pinfunction "2_2") (pintype "passive"))
      (node (ref "R8") (pin "1") (pinfunction "1_1") (pintype "passive"))
    )
    (net (code "19") (name "Net-(C11-Pad2)") (class "Default")
      (node (ref "C11") (pin "2") (pinfunction "2_2") (pintype "passive"))
      (node (ref "R9") (pin "1") (pinfunction "1_1") (pintype "passive"))
    )
    (net (code "20") (name "Net-(C30-Pad1)") (class "Default")
      (node (ref "C30") (pin "1") (pinfunction "1_1") (pintype "passive"))
      (node (ref "IC4") (pin "6") (pinfunction "INN_6") (pintype "bidirectional"))
      (node (ref "IC4") (pin "9") (pinfunction "INN_9") (pintype "bidirectional"))
      (node (ref "IC4") (pin "EP9") (pinfunction "INN_EP9") (pintype "bidirectional"))
      (node (ref "L4") (pin "2") (pinfunction "2_2") (pintype "passive"))
    )
    (net (code "21") (name "Net-(C40-Pad+)") (class "Default")
      (node (ref "C40") (pin "+") (pinfunction "+_+") (pintype "passive"))
      (node (ref "C41") (pin "1") (pinfunction "1_1") (pintype "passive"))
      (node (ref "R36") (pin "1") (pinfunction "1_1") (pintype "passive"))
    )
    (net (code "22") (name "Net-(C40-Pad-)") (class "Default")
      (node (ref "C40") (pin "-") (pinfunction "-_-") (pintype "passive"))
      (node (ref "X3") (pin "R") (pinfunction "R_R") (pintype "passive"))
      (node (ref "X3") (pin "T") (pinfunction "T_T") (pintype "passive"))
    )
    (net (code "23") (name "Net-(D1-PadA)") (class "Default")
      (node (ref "D1") (pin "A") (pinfunction "A_A") (pintype "passive"))
      (node (ref "IC2") (pin "1") (pinfunction "INP_1") (pintype "bidirectional"))
      (node (ref "IC2") (pin "24") (pinfunction "INP_24") (pintype "bidirectional"))
      (node (ref "L3") (pin "2") (pinfunction "2_2") (pintype "passive"))
    )
    (net (code "24") (name "Net-(D2-PadC)") (class "Default")
      (node (ref "D2") (pin "C") (pinfunction "C_C") (pintype "passive"))
      (node (ref "IC2") (pin "13") (pinfunction "OUTN_13") (pintype "bidirectional"))
      (node (ref "IC2") (pin "14") (pinfunction "OUTN_14") (pintype "bidirectional"))
      (node (ref "L6") (pin "2") (pinfunction "2_2") (pintype "passive"))
    )
    (net (code "25") (name "Net-(DISPLAY2A-CLK)") (class "Default")
      (node (ref "DISPLAY2") (pin "18") (pinfunction "CLK_18") (pintype "bidirectional"))
      (node (ref "DISPLAY2") (pin "32") (pinfunction "CLK_32") (pintype "bidirectional"))
    )
    (net (code "26") (name "Net-(DISPLAY2A-DIN)") (class "Default")
      (node (ref "DISPLAY2") (pin "22") (pinfunction "DIN_22") (pintype "bidirectional"))
      (node (ref "DISPLAY2") (pin "34") (pinfunction "MOSI_34") (pintype "bidirectional"))
    )
    (net (code "27") (name "Net-(DISPLAY2A-DOUT)") (class "Default")
      (node (ref "DISPLAY2") (pin "26") (pinfunction "DOUT_26") (pintype "bidirectional"))
      (node (ref "DISPLAY2") (pin "30") (pinfunction "MISO_30") (pintype "bidirectional"))
    )
    (net (code "28") (name "Net-(DISPLAY2D-LED_A+)") (class "Default")
      (node (ref "DISPLAY2") (pin "37") (pinfunction "LED_A+_37") (pintype "bidirectional"))
      (node (ref "R30") (pin "1") (pinfunction "1_1") (pintype "passive"))
    )
    (net (code "29") (name "Net-(I+-P)") (class "Default")
      (node (ref "I+") (pin "1") (pinfunction "P_1") (pintype "passive"))
      (node (ref "R11") (pin "2") (pinfunction "2_2") (pintype "passive"))
      (node (ref "R16") (pin "2") (pinfunction "2_2") (pintype "passive"))
    )
    (net (code "30") (name "Net-(I--P)") (class "Default")
      (node (ref "I-") (pin "1") (pinfunction "P_1") (pintype "passive"))
      (node (ref "IC1") (pin "10") (pinfunction "INN1_10") (pintype "bidirectional"))
      (node (ref "R17") (pin "2") (pinfunction "2_2") (pintype "passive"))
      (node (ref "R24") (pin "2") (pinfunction "2_2") (pintype "passive"))
      (node (ref "R25") (pin "2") (pinfunction "2_2") (pintype "passive"))
      (node (ref "R26") (pin "2") (pinfunction "2_2") (pintype "passive"))
      (node (ref "R27") (pin "2") (pinfunction "2_2") (pintype "passive"))
      (node (ref "R28") (pin "2") (pinfunction "2_2") (pintype "passive"))
    )
    (net (code "31") (name "Net-(IC1A-INN2)") (class "Default")
      (node (ref "C18") (pin "1") (pinfunction "1_1") (pintype "passive"))
      (node (ref "IC1") (pin "8") (pinfunction "INN2_8") (pintype "bidirectional"))
    )
    (net (code "32") (name "Net-(IC1A-INP1)") (class "Default")
      (node (ref "IC1") (pin "9") (pinfunction "INP1_9") (pintype "bidirectional"))
      (node (ref "IC8") (pin "8") (pinfunction "DA_8") (pintype "bidirectional"))
    )
    (net (code "33") (name "Net-(IC1A-INP2)") (class "Default")
      (node (ref "C16") (pin "2") (pinfunction "2_2") (pintype "passive"))
      (node (ref "IC1") (pin "7") (pinfunction "INP2_7") (pintype "bidirectional"))
    )
    (net (code "34") (name "Net-(IC1A-VOCM)") (class "Default")
      (node (ref "IC1") (pin "3") (pinfunction "VOCM_3") (pintype "bidirectional"))
      (node (ref "R14") (pin "1") (pinfunction "1_1") (pintype "passive"))
      (node (ref "R15") (pin "2") (pinfunction "2_2") (pintype "passive"))
    )
    (net (code "35") (name "Net-(IC1A-VON)") (class "Default")
      (node (ref "IC1") (pin "1") (pinfunction "VON_1") (pintype "bidirectional"))
      (node (ref "R2") (pin "1") (pinfunction "1_1") (pintype "passive"))
    )
    (net (code "36") (name "Net-(IC1A-VOP)") (class "Default")
      (node (ref "IC1") (pin "2") (pinfunction "VOP_2") (pintype "bidirectional"))
      (node (ref "R1") (pin "1") (pinfunction "1_1") (pintype "passive"))
    )
    (net (code "37") (name "Net-(IC2-CN)") (class "Default")
      (node (ref "C4") (pin "1") (pinfunction "1_1") (pintype "passive"))
      (node (ref "IC2") (pin "18") (pinfunction "CN_18") (pintype "bidirectional"))
    )
    (net (code "38") (name "Net-(IC2-CP)") (class "Default")
      (node (ref "C3") (pin "1") (pinfunction "1_1") (pintype "passive"))
      (node (ref "IC2") (pin "21") (pinfunction "CP_21") (pintype "bidirectional"))
    )
    (net (code "39") (name "Net-(IC2-FBN)") (class "Default")
      (node (ref "C28") (pin "1") (pinfunction "1_1") (pintype "passive"))
      (node (ref "IC2") (pin "16") (pinfunction "FBN_16") (pintype "bidirectional"))
      (node (ref "R31") (pin "1") (pinfunction "1_1") (pintype "passive"))
      (node (ref "R6") (pin "1") (pinfunction "1_1") (pintype "passive"))
    )
    (net (code "40") (name "Net-(IC2-FBP)") (class "Default")
      (node (ref "C7") (pin "2") (pinfunction "2_2") (pintype "passive"))
      (node (ref "IC2") (pin "22") (pinfunction "FBP_22") (pintype "bidirectional"))
      (node (ref "R4") (pin "2") (pinfunction "2_2") (pintype "passive"))
      (node (ref "R5") (pin "1") (pinfunction "1_1") (pintype "passive"))
    )
    (net (code "41") (name "Net-(IC2-VIN)") (class "Default")
      (node (ref "C2") (pin "1") (pinfunction "1_1") (pintype "passive"))
      (node (ref "IC2") (pin "4") (pinfunction "VIN_4") (pintype "bidirectional"))
      (node (ref "R3") (pin "1") (pinfunction "1_1") (pintype "passive"))
    )
    (net (code "42") (name "Net-(IC2-VNEG)") (class "Default")
      (node (ref "C27") (pin "1") (pinfunction "1_1") (pintype "passive"))
      (node (ref "C28") (pin "2") (pinfunction "2_2") (pintype "passive"))
      (node (ref "D2") (pin "A") (pinfunction "A_A") (pintype "passive"))
      (node (ref "IC2") (pin "15") (pinfunction "VNEG_15") (pintype "bidirectional"))
      (node (ref "L8") (pin "1") (pinfunction "1_1") (pintype "passive"))
      (node (ref "R6") (pin "2") (pinfunction "2_2") (pintype "passive"))
    )
    (net (code "43") (name "Net-(IC2-VPOS)") (class "Default")
      (node (ref "C7") (pin "1") (pinfunction "1_1") (pintype "passive"))
      (node (ref "C8") (pin "1") (pinfunction "1_1") (pintype "passive"))
      (node (ref "D1") (pin "C") (pinfunction "C_C") (pintype "passive"))
      (node (ref "IC2") (pin "23") (pinfunction "VPOS_23") (pintype "bidirectional"))
      (node (ref "L7") (pin "1") (pinfunction "1_1") (pintype "passive"))
      (node (ref "R4") (pin "1") (pinfunction "1_1") (pintype "passive"))
    )
    (net (code "44") (name "Net-(IC2-VREF)") (class "Default")
      (node (ref "C29") (pin "1") (pinfunction "1_1") (pintype "passive"))
      (node (ref "IC2") (pin "17") (pinfunction "VREF_17") (pintype "bidirectional"))
      (node (ref "R31") (pin "2") (pinfunction "2_2") (pintype "passive"))
    )
    (net (code "45") (name "Net-(IC3A-+IN)") (class "Default")
      (node (ref "C10") (pin "1") (pinfunction "1_1") (pintype "passive"))
      (node (ref "IC3") (pin "10") (pinfunction "+IN_10") (pintype "input"))
      (node (ref "IC3") (pin "3") (pinfunction "+IN_3") (pintype "input"))
      (node (ref "R8") (pin "2") (pinfunction "2_2") (pintype "passive"))
    )
    (net (code "46") (name "Net-(IC3A--IN)") (class "Default")
      (node (ref "C9") (pin "1") (pinfunction "1_1") (pintype "passive"))
      (node (ref "IC3") (pin "1") (pinfunction "OUT_1") (pintype "output"))
      (node (ref "IC3") (pin "2") (pinfunction "-IN_2") (pintype "input"))
    )
    (net (code "47") (name "Net-(IC3B--IN)") (class "Default")
      (node (ref "IC3") (pin "6") (pinfunction "-IN_6") (pintype "input"))
      (node (ref "IC3") (pin "7") (pinfunction "OUT_7") (pintype "output"))
      (node (ref "R7") (pin "1") (pinfunction "1_1") (pintype "passive"))
    )
    (net (code "48") (name "Net-(IC3C--IN)") (class "Default")
      (node (ref "C11") (pin "1") (pinfunction "1_1") (pintype "passive"))
      (node (ref "IC3") (pin "8") (pinfunction "OUT_8") (pintype "output"))
      (node (ref "IC3") (pin "9") (pinfunction "-IN_9") (pintype "input"))
    )
    (net (code "49") (name "Net-(IC3D--IN)") (class "Default")
      (node (ref "C38") (pin "2") (pinfunction "2_2") (pintype "passive"))
      (node (ref "IC3") (pin "13") (pinfunction "-IN_13") (pintype "input"))
      (node (ref "R34") (pin "2") (pinfunction "2_2") (pintype "passive"))
      (node (ref "R35") (pin "2") (pinfunction "2_2") (pintype "passive"))
    )
    (net (code "50") (name "Net-(IC3D-OUT)") (class "Default")
      (node (ref "C38") (pin "1") (pinfunction "1_1") (pintype "passive"))
      (node (ref "IC3") (pin "14") (pinfunction "OUT_14") (pintype "output"))
      (node (ref "IC7") (pin "3") (pinfunction "+IN_3") (pintype "input"))
      (node (ref "R35") (pin "1") (pinfunction "1_1") (pintype "passive"))
    )
    (net (code "51") (name "Net-(IC4-BYPN)") (class "Default")
      (node (ref "C45") (pin "1") (pinfunction "1_1") (pintype "passive"))
      (node (ref "IC4") (pin "11") (pinfunction "BYPN_11") (pintype "bidirectional"))
    )
    (net (code "52") (name "Net-(IC4-BYPP)") (class "Default")
      (node (ref "C46") (pin "2") (pinfunction "2_2") (pintype "passive"))
      (node (ref "IC4") (pin "3") (pinfunction "BYPP_3") (pintype "bidirectional"))
    )
    (net (code "53") (name "Net-(IC4-INP)") (class "Default")
      (node (ref "C31") (pin "1") (pinfunction "1_1") (pintype "passive"))
      (node (ref "IC4") (pin "14") (pinfunction "INP_14") (pintype "bidirectional"))
      (node (ref "L1") (pin "2") (pinfunction "2_2") (pintype "passive"))
    )
    (net (code "54") (name "Net-(IC5-EN)") (class "Default")
      (node (ref "C17") (pin "1") (pinfunction "1_1") (pintype "passive"))
      (node (ref "IC5") (pin "1") (pinfunction "VIN_1") (pintype "power_in"))
      (node (ref "IC5") (pin "3") (pinfunction "EN_3") (pintype "input"))
      (node (ref "L5") (pin "2") (pinfunction "2_2") (pintype "passive"))
    )
    (net (code "55") (name "Net-(IC6A-NRST)") (class "Default")
      (node (ref "C25") (pin "1") (pinfunction "1_1") (pintype "passive"))
      (node (ref "IC6") (pin "14") (pinfunction "NRST_14") (pintype "bidirectional"))
      (node (ref "R29") (pin "2") (pinfunction "2_2") (pintype "passive"))
    )
    (net (code "56") (name "Net-(IC6A-OSC_IN)") (class "Default")
      (node (ref "C15") (pin "1") (pinfunction "1_1") (pintype "passive"))
      (node (ref "IC6") (pin "12") (pinfunction "OSC_IN_12") (pintype "bidirectional"))
      (node (ref "Y1") (pin "3") (pinfunction "2_3") (pintype "passive"))
    )
    (net (code "57") (name "Net-(IC6A-OSC_OUT)") (class "Default")
      (node (ref "C14") (pin "1") (pinfunction "1_1") (pintype "passive"))
      (node (ref "IC6") (pin "13") (pinfunction "OSC_OUT_13") (pintype "bidirectional"))
      (node (ref "Y1") (pin "1") (pinfunction "1_1") (pintype "passive"))
    )
    (net (code "58") (name "Net-(IC6A-PA9)") (class "Default")
      (node (ref "IC6") (pin "68") (pinfunction "PA9_68") (pintype "bidirectional"))
      (node (ref "UART") (pin "3") (pinfunction "3_3") (pintype "passive"))
    )
    (net (code "59") (name "Net-(IC6A-PA10)") (class "Default")
      (node (ref "IC6") (pin "69") (pinfunction "PA10_69") (pintype "bidirectional"))
      (node (ref "UART") (pin "1") (pinfunction "1_1") (pintype "passive"))
    )
    (net (code "60") (name "Net-(IC6A-VDDA)") (class "Default")
      (node (ref "C20") (pin "1") (pinfunction "1_1") (pintype "passive"))
      (node (ref "IC6") (pin "22") (pinfunction "VDDA_22") (pintype "power_in"))
      (node (ref "L2") (pin "2") (pinfunction "2_2") (pintype "passive"))
    )
    (net (code "61") (name "Net-(IC7A--IN)") (class "Default")
      (node (ref "C12") (pin "2") (pinfunction "2_2") (pintype "passive"))
      (node (ref "IC7") (pin "2") (pinfunction "-IN_2") (pintype "input"))
      (node (ref "R10") (pin "1") (pinfunction "1_1") (pintype "passive"))
      (node (ref "R9") (pin "2") (pinfunction "2_2") (pintype "passive"))
    )
    (net (code "62") (name "Net-(IC7A-OUT)") (class "Default")
      (node (ref "C12") (pin "1") (pinfunction "1_1") (pintype "passive"))
      (node (ref "IC7") (pin "1") (pinfunction "OUT_1") (pintype "output"))
      (node (ref "R10") (pin "2") (pinfunction "2_2") (pintype "passive"))
      (node (ref "R11") (pin "1") (pinfunction "1_1") (pintype "passive"))
    )
    (net (code "63") (name "Net-(IC7B-+IN)") (class "Default")
      (node (ref "IC7") (pin "5") (pinfunction "+IN_5") (pintype "input"))
      (node (ref "R23") (pin "1") (pinfunction "1_1") (pintype "passive"))
    )
    (net (code "64") (name "Net-(IC7B--IN)") (class "Default")
      (node (ref "C13") (pin "2") (pinfunction "2_2") (pintype "passive"))
      (node (ref "IC7") (pin "6") (pinfunction "-IN_6") (pintype "input"))
      (node (ref "R28") (pin "1") (pinfunction "1_1") (pintype "passive"))
    )
    (net (code "65") (name "Net-(IC7B-OUT)") (class "Default")
      (node (ref "C13") (pin "1") (pinfunction "1_1") (pintype "passive"))
      (node (ref "IC7") (pin "7") (pinfunction "OUT_7") (pintype "output"))
      (node (ref "IC8") (pin "9") (pinfunction "DB_9") (pintype "bidirectional"))
    )
    (net (code "66") (name "Net-(IC8-S1A)") (class "Default")
      (node (ref "IC8") (pin "13") (pinfunction "S1B_13") (pintype "bidirectional"))
      (node (ref "IC8") (pin "4") (pinfunction "S1A_4") (pintype "bidirectional"))
      (node (ref "R27") (pin "1") (pinfunction "1_1") (pintype "passive"))
    )
    (net (code "67") (name "Net-(IC8-S2A)") (class "Default")
      (node (ref "IC8") (pin "12") (pinfunction "S2B_12") (pintype "bidirectional"))
      (node (ref "IC8") (pin "5") (pinfunction "S2A_5") (pintype "bidirectional"))
      (node (ref "R26") (pin "1") (pinfunction "1_1") (pintype "passive"))
    )
    (net (code "68") (name "Net-(IC8-S3A)") (class "Default")
      (node (ref "IC8") (pin "11") (pinfunction "S3B_11") (pintype "bidirectional"))
      (node (ref "IC8") (pin "6") (pinfunction "S3A_6") (pintype "bidirectional"))
      (node (ref "R25") (pin "1") (pinfunction "1_1") (pintype "passive"))
    )
    (net (code "69") (name "Net-(IC8-S4A)") (class "Default")
      (node (ref "IC8") (pin "10") (pinfunction "S4B_10") (pintype "bidirectional"))
      (node (ref "IC8") (pin "7") (pinfunction "S4A_7") (pintype "bidirectional"))
      (node (ref "R24") (pin "1") (pinfunction "1_1") (pintype "passive"))
    )
    (net (code "70") (name "Net-(L1-Pad1)") (class "Default")
      (node (ref "L1") (pin "1") (pinfunction "1_1") (pintype "passive"))
      (node (ref "L7") (pin "2") (pinfunction "2_2") (pintype "passive"))
    )
    (net (code "71") (name "Net-(L4-Pad1)") (class "Default")
      (node (ref "L4") (pin "1") (pinfunction "1_1") (pintype "passive"))
      (node (ref "L8") (pin "2") (pinfunction "2_2") (pintype "passive"))
    )
    (net (code "72") (name "Net-(R21-Pad2)") (class "Default")
      (node (ref "R21") (pin "2") (pinfunction "2_2") (pintype "passive"))
      (node (ref "X1") (pin "2") (pinfunction "2_2") (pintype "passive"))
    )
    (net (code "73") (name "Net-(R22-Pad2)") (class "Default")
      (node (ref "R22") (pin "2") (pinfunction "2_2") (pintype "passive"))
      (node (ref "X1") (pin "3") (pinfunction "3_3") (pintype "passive"))
    )
    (net (code "74") (name "Net-(U+-P)") (class "Default")
      (node (ref "C16") (pin "1") (pinfunction "1_1") (pintype "passive"))
      (node (ref "R16") (pin "1") (pinfunction "1_1") (pintype "passive"))
      (node (ref "U+") (pin "1") (pinfunction "P_1") (pintype "passive"))
    )
    (net (code "75") (name "Net-(U--P)") (class "Default")
      (node (ref "C18") (pin "2") (pinfunction "2_2") (pintype "passive"))
      (node (ref "R17") (pin "1") (pinfunction "1_1") (pintype "passive"))
      (node (ref "U-") (pin "1") (pinfunction "P_1") (pintype "passive"))
    )
    (net (code "76") (name "Net-(U1-FILTER)") (class "Default")
      (node (ref "C37") (pin "1") (pinfunction "1_1") (pintype "passive"))
      (node (ref "U1") (pin "1") (pinfunction "FILTER_1") (pintype "bidirectional"))
    )
    (net (code "77") (name "REF") (class "Default")
      (node (ref "C35") (pin "1") (pinfunction "1_1") (pintype "passive"))
      (node (ref "IC10") (pin "1") (pinfunction "REF_1") (pintype "bidirectional"))
      (node (ref "IC6") (pin "21") (pinfunction "VREF+_21") (pintype "power_in"))
      (node (ref "R14") (pin "2") (pinfunction "2_2") (pintype "passive"))
      (node (ref "U1") (pin "5") (pinfunction "OUTS_5") (pintype "bidirectional"))
      (node (ref "U1") (pin "6") (pinfunction "OUTF_6") (pintype "bidirectional"))
    )
    (net (code "78") (name "RELAIS") (class "Default")
      (node (ref "IC6") (pin "9") (pinfunction "PC15_9") (pintype "bidirectional"))
    )
    (net (code "79") (name "SCLK") (class "Default")
      (node (ref "IC1") (pin "16") (pinfunction "SCLK_16") (pintype "bidirectional"))
      (node (ref "IC6") (pin "89") (pinfunction "PB3_89") (pintype "bidirectional"))
    )
    (net (code "80") (name "SDI") (class "Default")
      (node (ref "IC1") (pin "15") (pinfunction "SDI_15") (pintype "bidirectional"))
      (node (ref "IC6") (pin "91") (pinfunction "PB5_91") (pintype "bidirectional"))
    )
    (net (code "81") (name "SDO") (class "Default")
      (node (ref "IC1") (pin "14") (pinfunction "SDO_14") (pintype "bidirectional"))
      (node (ref "IC6") (pin "90") (pinfunction "PB4_90") (pintype "bidirectional"))
    )
    (net (code "82") (name "SOUND") (class "Default")
      (node (ref "IC6") (pin "77") (pinfunction "PA15_77") (pintype "bidirectional"))
      (node (ref "R36") (pin "2") (pinfunction "2_2") (pintype "passive"))
    )
    (net (code "83") (name "SPLITSUPPLY_EN") (class "Default")
      (node (ref "IC2") (pin "10") (pinfunction "ENN_10") (pintype "bidirectional"))
      (node (ref "IC2") (pin "8") (pinfunction "ENP_8") (pintype "bidirectional"))
      (node (ref "IC4") (pin "10") (pinfunction "SHDNN_10") (pintype "bidirectional"))
      (node (ref "IC4") (pin "12") (pinfunction "SHDNP_12") (pintype "bidirectional"))
    )
    (net (code "84") (name "SPLITSUPPLY_PSE") (class "Default")
      (node (ref "IC2") (pin "11") (pinfunction "PSN_11") (pintype "bidirectional"))
      (node (ref "IC2") (pin "9") (pinfunction "PSP_9") (pintype "bidirectional"))
    )
    (net (code "85") (name "START") (class "Default")
      (node (ref "IC6") (pin "86") (pinfunction "PD5_86") (pintype "bidirectional"))
    )
    (net (code "86") (name "SWCLK") (class "Default")
      (node (ref "IC6") (pin "76") (pinfunction "PA14_76") (pintype "bidirectional"))
      (node (ref "UART1") (pin "1") (pinfunction "1_1") (pintype "passive"))
    )
    (net (code "87") (name "SWDIO") (class "Default")
      (node (ref "IC6") (pin "72") (pinfunction "PA13_72") (pintype "bidirectional"))
      (node (ref "UART1") (pin "3") (pinfunction "3_3") (pintype "passive"))
    )
    (net (code "88") (name "TFT_CS") (class "Default")
      (node (ref "DISPLAY2") (pin "29") (pinfunction "CS_29") (pintype "bidirectional"))
    )
    (net (code "89") (name "TFT_RD") (class "Default")
      (node (ref "DISPLAY2") (pin "11") (pinfunction "RD_11") (pintype "bidirectional"))
    )
    (net (code "90") (name "TFT_RS") (class "Default")
      (node (ref "DISPLAY2") (pin "7") (pinfunction "RS_7") (pintype "bidirectional"))
    )
    (net (code "91") (name "TFT_RST") (class "Default")
      (node (ref "DISPLAY2") (pin "33") (pinfunction "RST_33") (pintype "bidirectional"))
    )
    (net (code "92") (name "TFT_WR") (class "Default")
      (node (ref "DISPLAY2") (pin "9") (pinfunction "WR_9") (pintype "bidirectional"))
    )
    (net (code "93") (name "USB_N") (class "Default")
      (node (ref "IC6") (pin "70") (pinfunction "PA11_70") (pintype "bidirectional"))
      (node (ref "R21") (pin "1") (pinfunction "1_1") (pintype "passive"))
    )
    (net (code "94") (name "USB_P") (class "Default")
      (node (ref "IC6") (pin "71") (pinfunction "PA12_71") (pintype "bidirectional"))
      (node (ref "R22") (pin "1") (pinfunction "1_1") (pintype "passive"))
    )
    (net (code "95") (name "V+") (class "Default")
      (node (ref "C19") (pin "1") (pinfunction "1_1") (pintype "passive"))
      (node (ref "C34") (pin "1") (pinfunction "1_1") (pintype "passive"))
      (node (ref "C36") (pin "1") (pinfunction "1_1") (pintype "passive"))
      (node (ref "C5") (pin "1") (pinfunction "1_1") (pintype "passive"))
      (node (ref "IC1") (pin "4") (pinfunction "VSOP_4") (pintype "bidirectional"))
      (node (ref "IC10") (pin "2") (pinfunction "AVDD_2") (pintype "bidirectional"))
      (node (ref "IC5") (pin "5") (pinfunction "VOUT_5") (pintype "power_in"))
      (node (ref "U1") (pin "3") (pinfunction "EN_3") (pintype "bidirectional"))
      (node (ref "U1") (pin "4") (pinfunction "VIN_4") (pintype "bidirectional"))
    )
    (net (code "96") (name "unconnected-(DISPLAY2A-BUSY-Pad24)") (class "Default")
      (node (ref "DISPLAY2") (pin "24") (pinfunction "BUSY_24") (pintype "bidirectional"))
    )
    (net (code "97") (name "unconnected-(DISPLAY2A-CS-Pad20)") (class "Default")
      (node (ref "DISPLAY2") (pin "20") (pinfunction "CS_20") (pintype "bidirectional"))
    )
    (net (code "98") (name "unconnected-(DISPLAY2A-IRQ-Pad28)") (class "Default")
      (node (ref "DISPLAY2") (pin "28") (pinfunction "IRQ_28") (pintype "bidirectional"))
    )
    (net (code "99") (name "unconnected-(DISPLAY2B-CS-Pad36)") (class "Default")
      (node (ref "DISPLAY2") (pin "36") (pinfunction "CS_36") (pintype "bidirectional"))
    )
    (net (code "100") (name "unconnected-(DISPLAY2C-DB0-Pad2)") (class "Default")
      (node (ref "DISPLAY2") (pin "2") (pinfunction "DB0_2") (pintype "bidirectional"))
    )
    (net (code "101") (name "unconnected-(DISPLAY2C-DB1-Pad4)") (class "Default")
      (node (ref "DISPLAY2") (pin "4") (pinfunction "DB1_4") (pintype "bidirectional"))
    )
    (net (code "102") (name "unconnected-(DISPLAY2C-DB2-Pad6)") (class "Default")
      (node (ref "DISPLAY2") (pin "6") (pinfunction "DB2_6") (pintype "bidirectional"))
    )
    (net (code "103") (name "unconnected-(DISPLAY2C-DB3-Pad8)") (class "Default")
      (node (ref "DISPLAY2") (pin "8") (pinfunction "DB3_8") (pintype "bidirectional"))
    )
    (net (code "104") (name "unconnected-(DISPLAY2C-DB4-Pad10)") (class "Default")
      (node (ref "DISPLAY2") (pin "10") (pinfunction "DB4_10") (pintype "bidirectional"))
    )
    (net (code "105") (name "unconnected-(DISPLAY2C-DB5-Pad12)") (class "Default")
      (node (ref "DISPLAY2") (pin "12") (pinfunction "DB5_12") (pintype "bidirectional"))
    )
    (net (code "106") (name "unconnected-(DISPLAY2C-DB6-Pad14)") (class "Default")
      (node (ref "DISPLAY2") (pin "14") (pinfunction "DB6_14") (pintype "bidirectional"))
    )
    (net (code "107") (name "unconnected-(DISPLAY2C-DB7-Pad16)") (class "Default")
      (node (ref "DISPLAY2") (pin "16") (pinfunction "DB7_16") (pintype "bidirectional"))
    )
    (net (code "108") (name "unconnected-(DISPLAY2C-DB8-Pad13)") (class "Default")
      (node (ref "DISPLAY2") (pin "13") (pinfunction "DB8_13") (pintype "bidirectional"))
    )
    (net (code "109") (name "unconnected-(DISPLAY2C-DB9-Pad15)") (class "Default")
      (node (ref "DISPLAY2") (pin "15") (pinfunction "DB9_15") (pintype "bidirectional"))
    )
    (net (code "110") (name "unconnected-(DISPLAY2C-DB10-Pad17)") (class "Default")
      (node (ref "DISPLAY2") (pin "17") (pinfunction "DB10_17") (pintype "bidirectional"))
    )
    (net (code "111") (name "unconnected-(DISPLAY2C-DB11-Pad19)") (class "Default")
      (node (ref "DISPLAY2") (pin "19") (pinfunction "DB11_19") (pintype "bidirectional"))
    )
    (net (code "112") (name "unconnected-(DISPLAY2C-DB12-Pad21)") (class "Default")
      (node (ref "DISPLAY2") (pin "21") (pinfunction "DB12_21") (pintype "bidirectional"))
    )
    (net (code "113") (name "unconnected-(DISPLAY2C-DB13-Pad23)") (class "Default")
      (node (ref "DISPLAY2") (pin "23") (pinfunction "DB13_23") (pintype "bidirectional"))
    )
    (net (code "114") (name "unconnected-(DISPLAY2C-DB14-Pad25)") (class "Default")
      (node (ref "DISPLAY2") (pin "25") (pinfunction "DB14_25") (pintype "bidirectional"))
    )
    (net (code "115") (name "unconnected-(DISPLAY2C-DB15-Pad27)") (class "Default")
      (node (ref "DISPLAY2") (pin "27") (pinfunction "DB15_27") (pintype "bidirectional"))
    )
    (net (code "116") (name "unconnected-(IC1B-GPIO0-Pad24)") (class "Default")
      (node (ref "IC1") (pin "24") (pinfunction "GPIO0_24") (pintype "bidirectional"))
    )
    (net (code "117") (name "unconnected-(IC1B-GPIO1-Pad23)") (class "Default")
      (node (ref "IC1") (pin "23") (pinfunction "GPIO1_23") (pintype "bidirectional"))
    )
    (net (code "118") (name "unconnected-(IC1B-GPIO2-Pad22)") (class "Default")
      (node (ref "IC1") (pin "22") (pinfunction "GPIO2_22") (pintype "bidirectional"))
    )
    (net (code "119") (name "unconnected-(IC1B-GPIO3-Pad21)") (class "Default")
      (node (ref "IC1") (pin "21") (pinfunction "GPIO3_21") (pintype "bidirectional"))
    )
    (net (code "120") (name "unconnected-(IC1B-GPIO4-Pad20)") (class "Default")
      (node (ref "IC1") (pin "20") (pinfunction "GPIO4_20") (pintype "bidirectional"))
    )
    (net (code "121") (name "unconnected-(IC1B-GPIO5-Pad19)") (class "Default")
      (node (ref "IC1") (pin "19") (pinfunction "GPIO5_19") (pintype "bidirectional"))
    )
    (net (code "122") (name "unconnected-(IC1B-GPIO6-Pad18)") (class "Default")
      (node (ref "IC1") (pin "18") (pinfunction "GPIO6_18") (pintype "bidirectional"))
    )
    (net (code "123") (name "unconnected-(IC2-BSW-Pad7)") (class "Default")
      (node (ref "IC2") (pin "7") (pinfunction "BSW_7") (pintype "bidirectional"))
    )
    (net (code "124") (name "unconnected-(IC6A-PA0-WKUP-Pad23)") (class "Default")
      (node (ref "IC6") (pin "23") (pinfunction "PA0-WKUP_23") (pintype "bidirectional"))
    )
    (net (code "125") (name "unconnected-(IC6A-PA1-Pad24)") (class "Default")
      (node (ref "IC6") (pin "24") (pinfunction "PA1_24") (pintype "bidirectional"))
    )
    (net (code "126") (name "unconnected-(IC6A-PA2-Pad25)") (class "Default")
      (node (ref "IC6") (pin "25") (pinfunction "PA2_25") (pintype "bidirectional"))
    )
    (net (code "127") (name "unconnected-(IC6A-PA3-Pad26)") (class "Default")
      (node (ref "IC6") (pin "26") (pinfunction "PA3_26") (pintype "bidirectional"))
    )
    (net (code "128") (name "unconnected-(IC6A-PA6-Pad31)") (class "Default")
      (node (ref "IC6") (pin "31") (pinfunction "PA6_31") (pintype "bidirectional"))
    )
    (net (code "129") (name "unconnected-(IC6A-PA7-Pad32)") (class "Default")
      (node (ref "IC6") (pin "32") (pinfunction "PA7_32") (pintype "bidirectional"))
    )
    (net (code "130") (name "unconnected-(IC6A-PA8-Pad67)") (class "Default")
      (node (ref "IC6") (pin "67") (pinfunction "PA8_67") (pintype "bidirectional"))
    )
    (net (code "131") (name "unconnected-(IC6A-PB0-Pad35)") (class "Default")
      (node (ref "IC6") (pin "35") (pinfunction "PB0_35") (pintype "bidirectional"))
    )
    (net (code "132") (name "unconnected-(IC6A-PB1-Pad36)") (class "Default")
      (node (ref "IC6") (pin "36") (pinfunction "PB1_36") (pintype "bidirectional"))
    )
    (net (code "133") (name "unconnected-(IC6A-PB2-Pad37)") (class "Default")
      (node (ref "IC6") (pin "37") (pinfunction "PB2_37") (pintype "bidirectional"))
    )
    (net (code "134") (name "unconnected-(IC6A-PB7-Pad93)") (class "Default")
      (node (ref "IC6") (pin "93") (pinfunction "PB7_93") (pintype "bidirectional"))
    )
    (net (code "135") (name "unconnected-(IC6A-PB8-Pad95)") (class "Default")
      (node (ref "IC6") (pin "95") (pinfunction "PB8_95") (pintype "bidirectional"))
    )
    (net (code "136") (name "unconnected-(IC6A-PB9-Pad96)") (class "Default")
      (node (ref "IC6") (pin "96") (pinfunction "PB9_96") (pintype "bidirectional"))
    )
    (net (code "137") (name "unconnected-(IC6A-PB10-Pad47)") (class "Default")
      (node (ref "IC6") (pin "47") (pinfunction "PB10_47") (pintype "bidirectional"))
    )
    (net (code "138") (name "unconnected-(IC6A-PB11-Pad48)") (class "Default")
      (node (ref "IC6") (pin "48") (pinfunction "PB11_48") (pintype "bidirectional"))
    )
    (net (code "139") (name "unconnected-(IC6A-PB12-Pad51)") (class "Default")
      (node (ref "IC6") (pin "51") (pinfunction "PB12_51") (pintype "bidirectional"))
    )
    (net (code "140") (name "unconnected-(IC6A-PB13-Pad52)") (class "Default")
      (node (ref "IC6") (pin "52") (pinfunction "PB13_52") (pintype "bidirectional"))
    )
    (net (code "141") (name "unconnected-(IC6A-PB14-Pad53)") (class "Default")
      (node (ref "IC6") (pin "53") (pinfunction "PB14_53") (pintype "bidirectional"))
    )
    (net (code "142") (name "unconnected-(IC6A-PB15-Pad54)") (class "Default")
      (node (ref "IC6") (pin "54") (pinfunction "PB15_54") (pintype "bidirectional"))
    )
    (net (code "143") (name "unconnected-(IC6A-PC0-Pad15)") (class "Default")
      (node (ref "IC6") (pin "15") (pinfunction "PC0_15") (pintype "bidirectional"))
    )
    (net (code "144") (name "unconnected-(IC6A-PC1-Pad16)") (class "Default")
      (node (ref "IC6") (pin "16") (pinfunction "PC1_16") (pintype "bidirectional"))
    )
    (net (code "145") (name "unconnected-(IC6A-PC2-Pad17)") (class "Default")
      (node (ref "IC6") (pin "17") (pinfunction "PC2_17") (pintype "bidirectional"))
    )
    (net (code "146") (name "unconnected-(IC6A-PC3-Pad18)") (class "Default")
      (node (ref "IC6") (pin "18") (pinfunction "PC3_18") (pintype "bidirectional"))
    )
    (net (code "147") (name "unconnected-(IC6A-PC4-Pad33)") (class "Default")
      (node (ref "IC6") (pin "33") (pinfunction "PC4_33") (pintype "bidirectional"))
    )
    (net (code "148") (name "unconnected-(IC6A-PC5-Pad34)") (class "Default")
      (node (ref "IC6") (pin "34") (pinfunction "PC5_34") (pintype "bidirectional"))
    )
    (net (code "149") (name "unconnected-(IC6A-PC6-Pad63)") (class "Default")
      (node (ref "IC6") (pin "63") (pinfunction "PC6_63") (pintype "bidirectional"))
    )
    (net (code "150") (name "unconnected-(IC6A-PC7-Pad64)") (class "Default")
      (node (ref "IC6") (pin "64") (pinfunction "PC7_64") (pintype "bidirectional"))
    )
    (net (code "151") (name "unconnected-(IC6A-PC8-Pad65)") (class "Default")
      (node (ref "IC6") (pin "65") (pinfunction "PC8_65") (pintype "bidirectional"))
    )
    (net (code "152") (name "unconnected-(IC6A-PC9-Pad66)") (class "Default")
      (node (ref "IC6") (pin "66") (pinfunction "PC9_66") (pintype "bidirectional"))
    )
    (net (code "153") (name "unconnected-(IC6A-PC10-Pad78)") (class "Default")
      (node (ref "IC6") (pin "78") (pinfunction "PC10_78") (pintype "bidirectional"))
    )
    (net (code "154") (name "unconnected-(IC6A-PC11-Pad79)") (class "Default")
      (node (ref "IC6") (pin "79") (pinfunction "PC11_79") (pintype "bidirectional"))
    )
    (net (code "155") (name "unconnected-(IC6A-PC12-Pad80)") (class "Default")
      (node (ref "IC6") (pin "80") (pinfunction "PC12_80") (pintype "bidirectional"))
    )
    (net (code "156") (name "unconnected-(IC6A-PC13-Pad7)") (class "Default")
      (node (ref "IC6") (pin "7") (pinfunction "PC13_7") (pintype "bidirectional"))
    )
    (net (code "157") (name "unconnected-(IC6A-PC14-Pad8)") (class "Default")
      (node (ref "IC6") (pin "8") (pinfunction "PC14_8") (pintype "bidirectional"))
    )
    (net (code "158") (name "unconnected-(IC6A-PD0-Pad81)") (class "Default")
      (node (ref "IC6") (pin "81") (pinfunction "PD0_81") (pintype "bidirectional"))
    )
    (net (code "159") (name "unconnected-(IC6A-PD1-Pad82)") (class "Default")
      (node (ref "IC6") (pin "82") (pinfunction "PD1_82") (pintype "bidirectional"))
    )
    (net (code "160") (name "unconnected-(IC6A-PD2-Pad83)") (class "Default")
      (node (ref "IC6") (pin "83") (pinfunction "PD2_83") (pintype "bidirectional"))
    )
    (net (code "161") (name "unconnected-(IC6A-PD3-Pad84)") (class "Default")
      (node (ref "IC6") (pin "84") (pinfunction "PD3_84") (pintype "bidirectional"))
    )
    (net (code "162") (name "unconnected-(IC6A-PD8-Pad55)") (class "Default")
      (node (ref "IC6") (pin "55") (pinfunction "PD8_55") (pintype "bidirectional"))
    )
    (net (code "163") (name "unconnected-(IC6A-PD9-Pad56)") (class "Default")
      (node (ref "IC6") (pin "56") (pinfunction "PD9_56") (pintype "bidirectional"))
    )
    (net (code "164") (name "unconnected-(IC6A-PD10-Pad57)") (class "Default")
      (node (ref "IC6") (pin "57") (pinfunction "PD10_57") (pintype "bidirectional"))
    )
    (net (code "165") (name "unconnected-(IC6A-PD11-Pad58)") (class "Default")
      (node (ref "IC6") (pin "58") (pinfunction "PD11_58") (pintype "bidirectional"))
    )
    (net (code "166") (name "unconnected-(IC6A-PD12-Pad59)") (class "Default")
      (node (ref "IC6") (pin "59") (pinfunction "PD12_59") (pintype "bidirectional"))
    )
    (net (code "167") (name "unconnected-(IC6A-PD15-Pad62)") (class "Default")
      (node (ref "IC6") (pin "62") (pinfunction "PD15_62") (pintype "bidirectional"))
    )
    (net (code "168") (name "unconnected-(IC6A-PE0-Pad97)") (class "Default")
      (node (ref "IC6") (pin "97") (pinfunction "PE0_97") (pintype "bidirectional"))
    )
    (net (code "169") (name "unconnected-(IC6A-PE1-Pad98)") (class "Default")
      (node (ref "IC6") (pin "98") (pinfunction "PE1_98") (pintype "bidirectional"))
    )
    (net (code "170") (name "unconnected-(IC6A-PE3-Pad2)") (class "Default")
      (node (ref "IC6") (pin "2") (pinfunction "PE3_2") (pintype "bidirectional"))
    )
    (net (code "171") (name "unconnected-(IC6A-PE7-Pad38)") (class "Default")
      (node (ref "IC6") (pin "38") (pinfunction "PE7_38") (pintype "bidirectional"))
    )
    (net (code "172") (name "unconnected-(IC6A-PE8-Pad39)") (class "Default")
      (node (ref "IC6") (pin "39") (pinfunction "PE8_39") (pintype "bidirectional"))
    )
    (net (code "173") (name "unconnected-(IC6A-PE9-Pad40)") (class "Default")
      (node (ref "IC6") (pin "40") (pinfunction "PE9_40") (pintype "bidirectional"))
    )
    (net (code "174") (name "unconnected-(IC6A-PE10-Pad41)") (class "Default")
      (node (ref "IC6") (pin "41") (pinfunction "PE10_41") (pintype "bidirectional"))
    )
    (net (code "175") (name "unconnected-(IC6A-PE11-Pad42)") (class "Default")
      (node (ref "IC6") (pin "42") (pinfunction "PE11_42") (pintype "bidirectional"))
    )
    (net (code "176") (name "unconnected-(IC6A-PE12-Pad43)") (class "Default")
      (node (ref "IC6") (pin "43") (pinfunction "PE12_43") (pintype "bidirectional"))
    )
    (net (code "177") (name "unconnected-(IC6A-PE13-Pad44)") (class "Default")
      (node (ref "IC6") (pin "44") (pinfunction "PE13_44") (pintype "bidirectional"))
    )
    (net (code "178") (name "unconnected-(IC6A-PE14-Pad45)") (class "Default")
      (node (ref "IC6") (pin "45") (pinfunction "PE14_45") (pintype "bidirectional"))
    )
    (net (code "179") (name "unconnected-(IC6A-PE15-Pad46)") (class "Default")
      (node (ref "IC6") (pin "46") (pinfunction "PE15_46") (pintype "bidirectional"))
    )
    (net (code "180") (name "unconnected-(IC6A-PF2-Pad19)") (class "Default")
      (node (ref "IC6") (pin "19") (pinfunction "PF2_19") (pintype "bidirectional"))
    )
    (net (code "181") (name "unconnected-(IC6A-PF4-Pad27)") (class "Default")
      (node (ref "IC6") (pin "27") (pinfunction "PF4_27") (pintype "bidirectional"))
    )
    (net (code "182") (name "unconnected-(IC6A-PF6-Pad73)") (class "Default")
      (node (ref "IC6") (pin "73") (pinfunction "PF6_73") (pintype "bidirectional"))
    )
    (net (code "183") (name "unconnected-(IC6A-PF9-Pad10)") (class "Default")
      (node (ref "IC6") (pin "10") (pinfunction "PF9_10") (pintype "bidirectional"))
    )
    (net (code "184") (name "unconnected-(IC6A-PF10-Pad11)") (class "Default")
      (node (ref "IC6") (pin "11") (pinfunction "PF10_11") (pintype "bidirectional"))
    )
    (net (code "185") (name "unconnected-(IC8-A0-Pad1)") (class "Default")
      (node (ref "IC8") (pin "1") (pinfunction "A0_1") (pintype "bidirectional"))
    )
    (net (code "186") (name "unconnected-(IC8-A1-Pad16)") (class "Default")
      (node (ref "IC8") (pin "16") (pinfunction "A1_16") (pintype "bidirectional"))
    )
    (net (code "187") (name "unconnected-(IC8-EN-Pad2)") (class "Default")
      (node (ref "IC8") (pin "2") (pinfunction "EN_2") (pintype "bidirectional"))
    )
    (net (code "188") (name "unconnected-(R12-Pad1)") (class "Default")
      (node (ref "R12") (pin "1") (pinfunction "1_1") (pintype "passive"))
    )
    (net (code "189") (name "unconnected-(R12-Pad2)") (class "Default")
      (node (ref "R12") (pin "2") (pinfunction "2_2") (pintype "passive"))
    )
    (net (code "190") (name "unconnected-(R13-Pad1)") (class "Default")
      (node (ref "R13") (pin "1") (pinfunction "1_1") (pintype "passive"))
    )
    (net (code "191") (name "unconnected-(R13-Pad2)") (class "Default")
      (node (ref "R13") (pin "2") (pinfunction "2_2") (pintype "passive"))
    )
    (net (code "192") (name "unconnected-(X1-Pad1)") (class "Default")
      (node (ref "X1") (pin "1") (pinfunction "1_1") (pintype "passive"))
    )
    (net (code "193") (name "unconnected-(X3-PadB)") (class "Default")
      (node (ref "X3") (pin "B") (pinfunction "B_B") (pintype "passive"))
    )
  )
)
